# 31813B.net
KiCad netlist of a schematic drawn in EAGLE
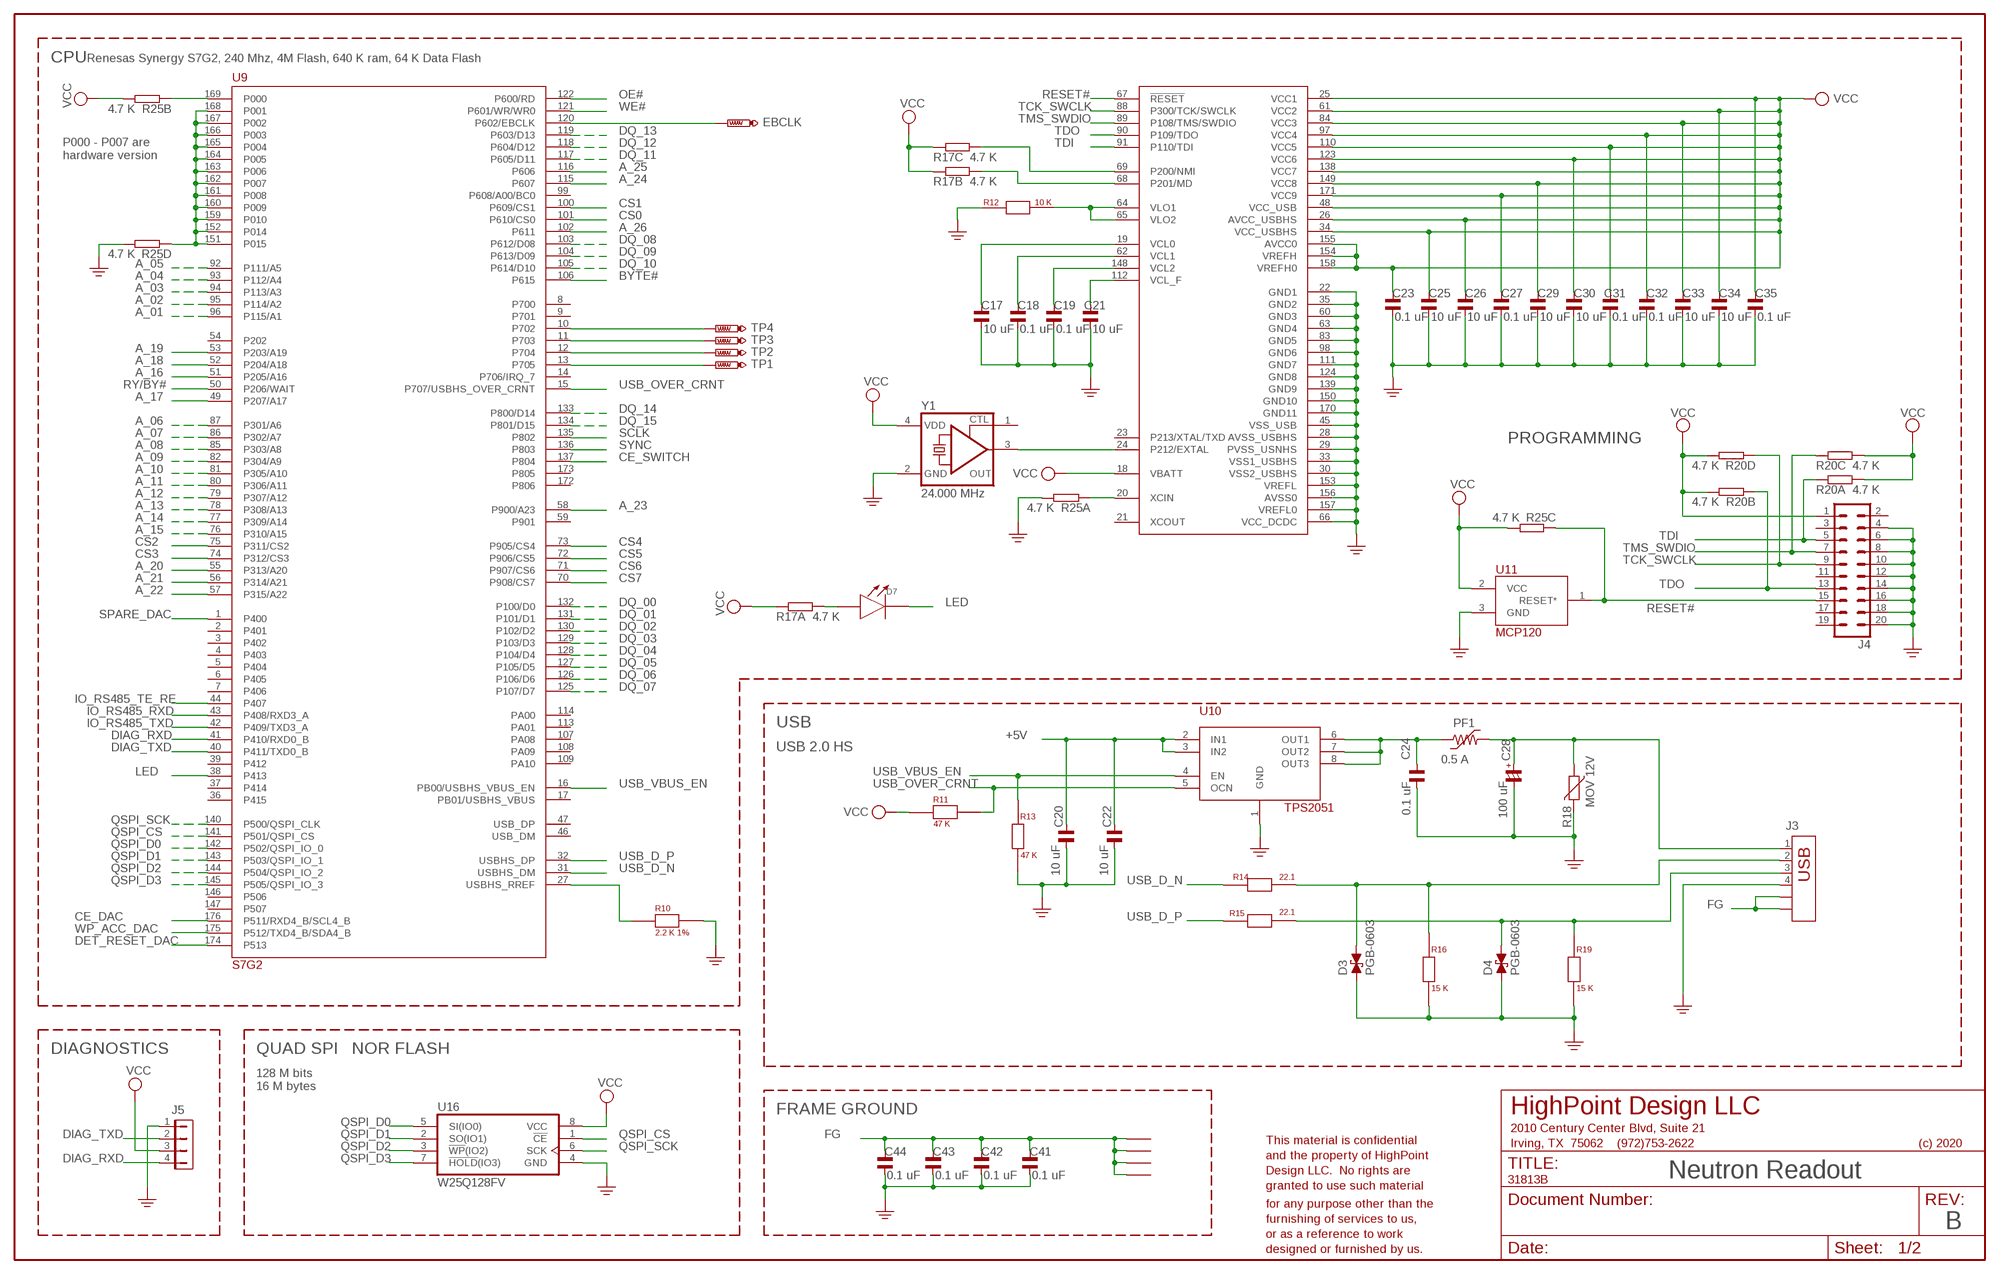
[diagram p0: schematic, sheet 1]
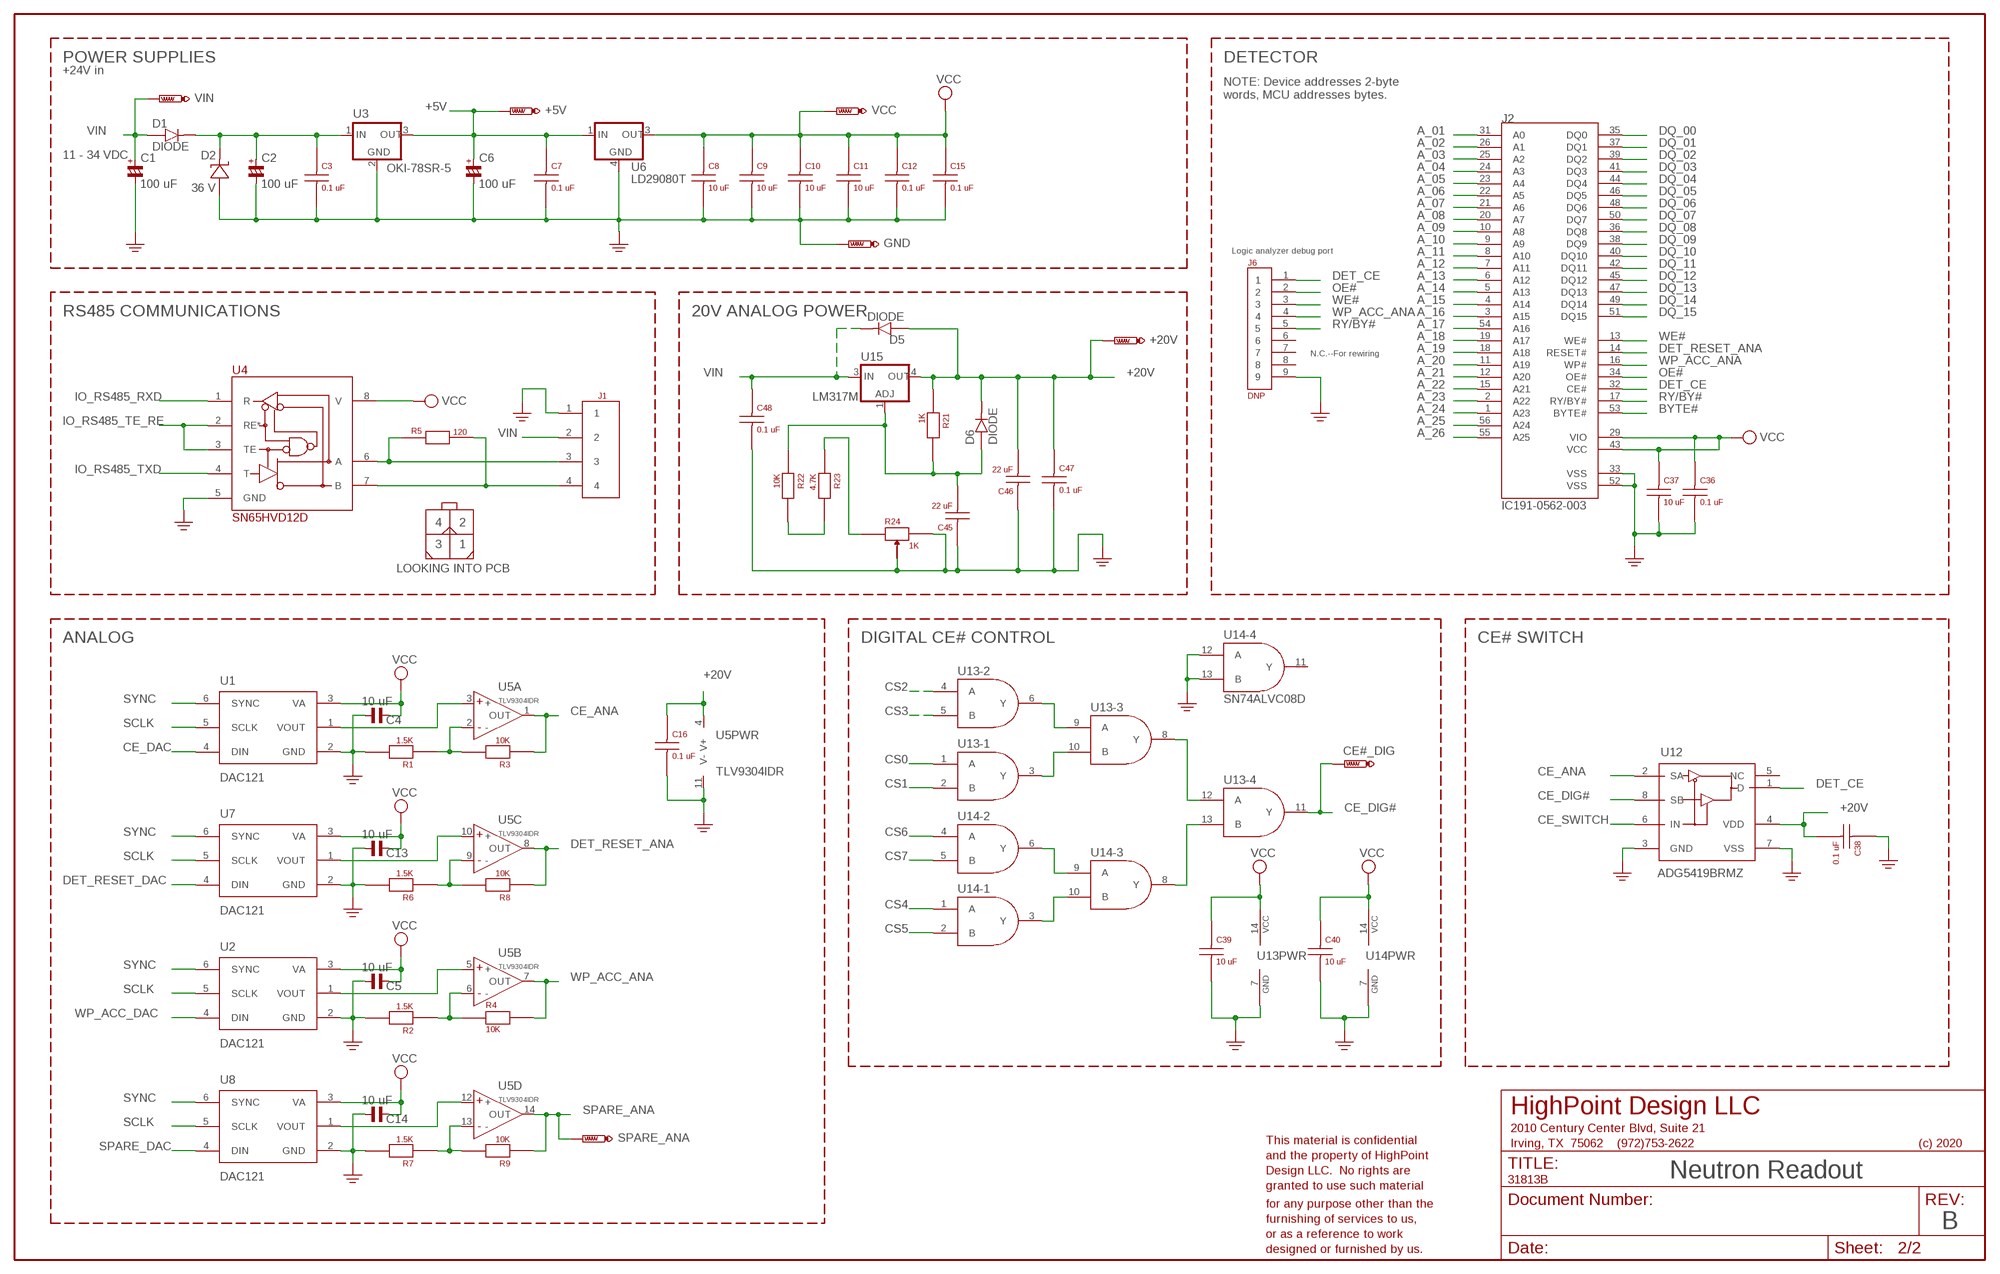
[diagram p1: schematic, sheet 2]

(export (version "E")
  (design (tool "Eeschema 10.0.6"))
  (components
    (comp (ref "C17")
      (value "10 uF")
      (footprint "eagle-import:0603")
      (libsource (lib "eagle-import") (part "CAP_SMD-0603"))
    )
    (comp (ref "C18")
      (value "0.1 uF")
      (footprint "eagle-import:0603")
      (libsource (lib "eagle-import") (part "CAP_SMD-0603"))
    )
    (comp (ref "C19")
      (value "0.1 uF")
      (footprint "eagle-import:0603")
      (libsource (lib "eagle-import") (part "CAP_SMD-0603"))
    )
    (comp (ref "C20")
      (value "10 uF")
      (footprint "eagle-import:0603")
      (libsource (lib "eagle-import") (part "CAP_SMD-0603"))
    )
    (comp (ref "C21")
      (value "10 uF")
      (footprint "eagle-import:0603")
      (libsource (lib "eagle-import") (part "CAP_SMD-0603"))
    )
    (comp (ref "C22")
      (value "10 uF")
      (footprint "eagle-import:0603")
      (libsource (lib "eagle-import") (part "CAP_SMD-0603"))
    )
    (comp (ref "C23")
      (value "0.1 uF")
      (footprint "eagle-import:0603")
      (libsource (lib "eagle-import") (part "CAP_SMD-0603"))
    )
    (comp (ref "C24")
      (value "0.1 uF")
      (footprint "eagle-import:0603")
      (libsource (lib "eagle-import") (part "CAP_SMD-0603"))
    )
    (comp (ref "C25")
      (value "10 uF")
      (footprint "eagle-import:0603")
      (libsource (lib "eagle-import") (part "CAP_SMD-0603"))
    )
    (comp (ref "C26")
      (value "10 uF")
      (footprint "eagle-import:0603")
      (libsource (lib "eagle-import") (part "CAP_SMD-0603"))
    )
    (comp (ref "C27")
      (value "0.1 uF")
      (footprint "eagle-import:0603")
      (libsource (lib "eagle-import") (part "CAP_SMD-0603"))
    )
    (comp (ref "C28")
      (value "100 uF")
      (footprint "eagle-import:CSV-E_F")
      (libsource (lib "eagle-import") (part "CAP_POL-E"))
    )
    (comp (ref "C29")
      (value "10 uF")
      (footprint "eagle-import:0603")
      (libsource (lib "eagle-import") (part "CAP_SMD-0603"))
    )
    (comp (ref "C30")
      (value "10 uF")
      (footprint "eagle-import:0603")
      (libsource (lib "eagle-import") (part "CAP_SMD-0603"))
    )
    (comp (ref "C31")
      (value "0.1 uF")
      (footprint "eagle-import:0603")
      (libsource (lib "eagle-import") (part "CAP_SMD-0603"))
    )
    (comp (ref "C32")
      (value "0.1 uF")
      (footprint "eagle-import:0603")
      (libsource (lib "eagle-import") (part "CAP_SMD-0603"))
    )
    (comp (ref "C33")
      (value "10 uF")
      (footprint "eagle-import:0603")
      (libsource (lib "eagle-import") (part "CAP_SMD-0603"))
    )
    (comp (ref "C34")
      (value "10 uF")
      (footprint "eagle-import:0603")
      (libsource (lib "eagle-import") (part "CAP_SMD-0603"))
    )
    (comp (ref "C35")
      (value "0.1 uF")
      (footprint "eagle-import:0603")
      (libsource (lib "eagle-import") (part "CAP_SMD-0603"))
    )
    (comp (ref "C41")
      (value "0.1 uF")
      (footprint "eagle-import:0603")
      (libsource (lib "eagle-import") (part "CAP_SMD-0603"))
    )
    (comp (ref "C42")
      (value "0.1 uF")
      (footprint "eagle-import:0603")
      (libsource (lib "eagle-import") (part "CAP_SMD-0603"))
    )
    (comp (ref "C43")
      (value "0.1 uF")
      (footprint "eagle-import:0603")
      (libsource (lib "eagle-import") (part "CAP_SMD-0603"))
    )
    (comp (ref "C44")
      (value "0.1 uF")
      (footprint "eagle-import:0603")
      (libsource (lib "eagle-import") (part "CAP_SMD-0603"))
    )
    (comp (ref "D3")
      (value "PGB-0603")
      (footprint "eagle-import:PGB-0603")
      (libsource (lib "eagle-import") (part "PGB-0603"))
    )
    (comp (ref "D4")
      (value "PGB-0603")
      (footprint "eagle-import:PGB-0603")
      (libsource (lib "eagle-import") (part "PGB-0603"))
    )
    (comp (ref "D7")
      (value "LED0805")
      (footprint "eagle-import:D0805")
      (libsource (lib "eagle-import") (part "LED0805"))
    )
    (comp (ref "EBCLK")
      (value "TP")
      (footprint "eagle-import:TP8040")
      (libsource (lib "eagle-import") (part "TP"))
    )
    (comp (ref "J3")
      (value "CON-USB-292303-1")
      (footprint "eagle-import:USB")
      (libsource (lib "eagle-import") (part "CON-USB-292303-1"))
    )
    (comp (ref "J4")
      (value "ML20")
      (footprint "eagle-import:ML20")
      (libsource (lib "eagle-import") (part "ML20"))
    )
    (comp (ref "J5")
      (value "MTA04")
      (footprint "eagle-import:MTA04-100")
      (libsource (lib "eagle-import") (part "MTA04"))
    )
    (comp (ref "M1")
      (value "MNT-125")
      (footprint "eagle-import:MNT-125")
      (libsource (lib "eagle-import") (part "MNT-125"))
    )
    (comp (ref "M2")
      (value "MNT-125")
      (footprint "eagle-import:MNT-125")
      (libsource (lib "eagle-import") (part "MNT-125"))
    )
    (comp (ref "M3")
      (value "MNT-125")
      (footprint "eagle-import:MNT-125")
      (libsource (lib "eagle-import") (part "MNT-125"))
    )
    (comp (ref "M4")
      (value "MNT-125")
      (footprint "eagle-import:MNT-125")
      (libsource (lib "eagle-import") (part "MNT-125"))
    )
    (comp (ref "PF1")
      (value "0.5 A")
      (footprint "eagle-import:F1206")
      (libsource (lib "eagle-import") (part "PTC-F1206"))
    )
    (comp (ref "R10")
      (value "2.2 K 1%")
      (footprint "eagle-import:0603")
      (libsource (lib "eagle-import") (part "RES-0603-H"))
    )
    (comp (ref "R11")
      (value "47 K")
      (footprint "eagle-import:0603")
      (libsource (lib "eagle-import") (part "RES-0603-H"))
    )
    (comp (ref "R12")
      (value "10 K")
      (footprint "eagle-import:0603")
      (libsource (lib "eagle-import") (part "RES-0603-H"))
    )
    (comp (ref "R13")
      (value "47 K")
      (footprint "eagle-import:0603")
      (libsource (lib "eagle-import") (part "RES-0603-V"))
    )
    (comp (ref "R14")
      (value "22.1")
      (footprint "eagle-import:0603")
      (libsource (lib "eagle-import") (part "RES-0603-H"))
    )
    (comp (ref "R15")
      (value "22.1")
      (footprint "eagle-import:0603")
      (libsource (lib "eagle-import") (part "RES-0603-H"))
    )
    (comp (ref "R16")
      (value "15 K")
      (footprint "eagle-import:0603")
      (libsource (lib "eagle-import") (part "RES-0603-V"))
    )
    (comp (ref "R17")
      (value "4.7 K")
      (footprint "eagle-import:RNET-4R-38V")
      (libsource (lib "eagle-import") (part "R_38V"))
    )
    (comp (ref "R18")
      (value "MOV 12V")
      (footprint "eagle-import:R0603")
      (libsource (lib "eagle-import") (part "VARISTOR-0603"))
    )
    (comp (ref "R19")
      (value "15 K")
      (footprint "eagle-import:0603")
      (libsource (lib "eagle-import") (part "RES-0603-V"))
    )
    (comp (ref "R20")
      (value "4.7 K")
      (footprint "eagle-import:RNET-4R-38V")
      (libsource (lib "eagle-import") (part "R_38V"))
    )
    (comp (ref "R25")
      (value "4.7 K")
      (footprint "eagle-import:RNET-4R-38V")
      (libsource (lib "eagle-import") (part "R_38V"))
    )
    (comp (ref "TP1")
      (value "TP")
      (footprint "eagle-import:TP8040")
      (libsource (lib "eagle-import") (part "TP"))
    )
    (comp (ref "TP2")
      (value "TP")
      (footprint "eagle-import:TP8040")
      (libsource (lib "eagle-import") (part "TP"))
    )
    (comp (ref "TP3")
      (value "TP")
      (footprint "eagle-import:TP8040")
      (libsource (lib "eagle-import") (part "TP"))
    )
    (comp (ref "TP4")
      (value "TP")
      (footprint "eagle-import:TP8040")
      (libsource (lib "eagle-import") (part "TP"))
    )
    (comp (ref "U9")
      (value "S7G2")
      (footprint "eagle-import:LQFP176")
      (libsource (lib "eagle-import") (part "S7G2-176"))
    )
    (comp (ref "U10")
      (value "TPS2051")
      (footprint "eagle-import:SOIC-8-SPECIAL")
      (libsource (lib "eagle-import") (part "TPS2051"))
    )
    (comp (ref "U11")
      (value "MCP120")
      (footprint "eagle-import:SOT23")
      (libsource (lib "eagle-import") (part "MCP120"))
    )
    (comp (ref "U16")
      (value "W25Q128FV")
      (footprint "eagle-import:SO08-JB")
      (libsource (lib "eagle-import") (part "IS25LQ080B-JB"))
    )
    (comp (ref "Y1")
      (value "24.000 MHz")
      (footprint "eagle-import:ASFL1")
      (libsource (lib "eagle-import") (part "ASFL1"))
    )
    (comp (ref "+5V")
      (value "TP")
      (footprint "eagle-import:TP8040")
      (libsource (lib "eagle-import") (part "TP"))
    )
    (comp (ref "+20V")
      (value "TP")
      (footprint "eagle-import:TP8040")
      (libsource (lib "eagle-import") (part "TP"))
    )
    (comp (ref "C1")
      (value "100 uF")
      (footprint "eagle-import:CSV-E_F")
      (libsource (lib "eagle-import") (part "CAP_POL-E"))
    )
    (comp (ref "C2")
      (value "100 uF")
      (footprint "eagle-import:CSV-E_F")
      (libsource (lib "eagle-import") (part "CAP_POL-E"))
    )
    (comp (ref "C3")
      (value "0.1 uF")
      (footprint "eagle-import:0603")
      (libsource (lib "eagle-import") (part "CAP-0603"))
    )
    (comp (ref "C4")
      (value "10 uF")
      (footprint "eagle-import:0603")
      (libsource (lib "eagle-import") (part "CAP_SMD-0603"))
    )
    (comp (ref "C5")
      (value "10 uF")
      (footprint "eagle-import:0603")
      (libsource (lib "eagle-import") (part "CAP_SMD-0603"))
    )
    (comp (ref "C6")
      (value "100 uF")
      (footprint "eagle-import:CSV-E_F")
      (libsource (lib "eagle-import") (part "CAP_POL-E"))
    )
    (comp (ref "C7")
      (value "0.1 uF")
      (footprint "eagle-import:0603")
      (libsource (lib "eagle-import") (part "CAP-0603"))
    )
    (comp (ref "C8")
      (value "10 uF")
      (footprint "eagle-import:0603")
      (libsource (lib "eagle-import") (part "CAP-0603"))
    )
    (comp (ref "C9")
      (value "10 uF")
      (footprint "eagle-import:0603")
      (libsource (lib "eagle-import") (part "CAP-0603"))
    )
    (comp (ref "C10")
      (value "10 uF")
      (footprint "eagle-import:0603")
      (libsource (lib "eagle-import") (part "CAP-0603"))
    )
    (comp (ref "C11")
      (value "10 uF")
      (footprint "eagle-import:0603")
      (libsource (lib "eagle-import") (part "CAP-0603"))
    )
    (comp (ref "C12")
      (value "0.1 uF")
      (footprint "eagle-import:0603")
      (libsource (lib "eagle-import") (part "CAP-0603"))
    )
    (comp (ref "C13")
      (value "10 uF")
      (footprint "eagle-import:0603")
      (libsource (lib "eagle-import") (part "CAP_SMD-0603"))
    )
    (comp (ref "C14")
      (value "10 uF")
      (footprint "eagle-import:0603")
      (libsource (lib "eagle-import") (part "CAP_SMD-0603"))
    )
    (comp (ref "C15")
      (value "0.1 uF")
      (footprint "eagle-import:0603")
      (libsource (lib "eagle-import") (part "CAP-0603"))
    )
    (comp (ref "C16")
      (value "0.1 uF")
      (footprint "eagle-import:0603")
      (libsource (lib "eagle-import") (part "CAP-0603"))
    )
    (comp (ref "C36")
      (value "0.1 uF")
      (footprint "eagle-import:0603")
      (libsource (lib "eagle-import") (part "CAP-0603"))
    )
    (comp (ref "C37")
      (value "10 uF")
      (footprint "eagle-import:0603")
      (libsource (lib "eagle-import") (part "CAP-0603"))
    )
    (comp (ref "C38")
      (value "0.1 uF")
      (footprint "eagle-import:0603")
      (libsource (lib "eagle-import") (part "CAP-0603"))
    )
    (comp (ref "C39")
      (value "10 uF")
      (footprint "eagle-import:0603")
      (libsource (lib "eagle-import") (part "CAP-0603"))
    )
    (comp (ref "C40")
      (value "10 uF")
      (footprint "eagle-import:0603")
      (libsource (lib "eagle-import") (part "CAP-0603"))
    )
    (comp (ref "C45")
      (value "22 uF")
      (footprint "eagle-import:C1206")
      (libsource (lib "eagle-import") (part "CAP-1206"))
    )
    (comp (ref "C46")
      (value "22 uF")
      (footprint "eagle-import:C1206")
      (libsource (lib "eagle-import") (part "CAP-1206"))
    )
    (comp (ref "C47")
      (value "0.1 uF")
      (footprint "eagle-import:0603")
      (libsource (lib "eagle-import") (part "CAP-0603"))
    )
    (comp (ref "C48")
      (value "0.1 uF")
      (footprint "eagle-import:0603")
      (libsource (lib "eagle-import") (part "CAP-0603"))
    )
    (comp (ref "CE#_DIG")
      (value "TP")
      (footprint "eagle-import:TP8040")
      (libsource (lib "eagle-import") (part "TP"))
    )
    (comp (ref "D1")
      (value "DIODE")
      (footprint "eagle-import:SOD-123_MINI-SMA")
      (libsource (lib "eagle-import") (part "DIODE"))
    )
    (comp (ref "D2")
      (value "36 V")
      (footprint "eagle-import:SMB")
      (libsource (lib "eagle-import") (part "TRANSORB"))
    )
    (comp (ref "D5")
      (value "DIODE")
      (footprint "eagle-import:SOD-123_MINI-SMA")
      (libsource (lib "eagle-import") (part "DIODE"))
    )
    (comp (ref "D6")
      (value "DIODE")
      (footprint "eagle-import:SOD-123_MINI-SMA")
      (libsource (lib "eagle-import") (part "DIODE"))
    )
    (comp (ref "GND")
      (value "TP")
      (footprint "eagle-import:TP8040")
      (libsource (lib "eagle-import") (part "TP"))
    )
    (comp (ref "J1")
      (value "MICRO-FIT-4POS")
      (footprint "eagle-import:43045-0412")
      (libsource (lib "eagle-import") (part "MICRO-FIT-4POS"))
    )
    (comp (ref "J2")
      (value "IC191-0562-003")
      (footprint "eagle-import:IC1910562003")
      (fields (field (name "MOUSER_PART_NUMBER") "945-IC191-0562-003"))
      (libsource (lib "eagle-import") (part "IC191-0562-003"))
    )
    (comp (ref "J6")
      (value "DNP")
      (footprint "eagle-import:9P-100")
      (libsource (lib "eagle-import") (part "CON-9P-100"))
    )
    (comp (ref "R1")
      (value "1.5K")
      (footprint "eagle-import:0603")
      (libsource (lib "eagle-import") (part "RES-0603-H"))
    )
    (comp (ref "R2")
      (value "1.5K")
      (footprint "eagle-import:0603")
      (libsource (lib "eagle-import") (part "RES-0603-H"))
    )
    (comp (ref "R3")
      (value "10K")
      (footprint "eagle-import:0603")
      (libsource (lib "eagle-import") (part "RES-0603-H"))
    )
    (comp (ref "R4")
      (value "10K")
      (footprint "eagle-import:0603")
      (libsource (lib "eagle-import") (part "RES-0603-H"))
    )
    (comp (ref "R5")
      (value "120")
      (footprint "eagle-import:0603")
      (libsource (lib "eagle-import") (part "RES-0603-H"))
    )
    (comp (ref "R6")
      (value "1.5K")
      (footprint "eagle-import:0603")
      (libsource (lib "eagle-import") (part "RES-0603-H"))
    )
    (comp (ref "R7")
      (value "1.5K")
      (footprint "eagle-import:0603")
      (libsource (lib "eagle-import") (part "RES-0603-H"))
    )
    (comp (ref "R8")
      (value "10K")
      (footprint "eagle-import:0603")
      (libsource (lib "eagle-import") (part "RES-0603-H"))
    )
    (comp (ref "R9")
      (value "10K")
      (footprint "eagle-import:0603")
      (libsource (lib "eagle-import") (part "RES-0603-H"))
    )
    (comp (ref "R21")
      (value "1K")
      (footprint "eagle-import:0603")
      (libsource (lib "eagle-import") (part "RES-0603-H"))
    )
    (comp (ref "R22")
      (value "10K")
      (footprint "eagle-import:0603")
      (libsource (lib "eagle-import") (part "RES-0603-H"))
    )
    (comp (ref "R23")
      (value "4.7K")
      (footprint "eagle-import:0603")
      (libsource (lib "eagle-import") (part "RES-0603-H"))
    )
    (comp (ref "R24")
      (value "1K")
      (footprint "eagle-import:POT-V10")
      (libsource (lib "eagle-import") (part "PT10XV10"))
    )
    (comp (ref "SPARE_ANA")
      (value "TP")
      (footprint "eagle-import:TP8040")
      (libsource (lib "eagle-import") (part "TP"))
    )
    (comp (ref "U1")
      (value "DAC121")
      (footprint "eagle-import:SOT23-6")
      (libsource (lib "eagle-import") (part "DAC121"))
    )
    (comp (ref "U2")
      (value "DAC121")
      (footprint "eagle-import:SOT23-6")
      (libsource (lib "eagle-import") (part "DAC121"))
    )
    (comp (ref "U3")
      (value "OKI-78SR-5")
      (footprint "eagle-import:PS-OKI-78SR")
      (libsource (lib "eagle-import") (part "PS-OKI-78SR"))
    )
    (comp (ref "U4")
      (value "SN65HVD12D")
      (footprint "eagle-import:SOIC-08-150")
      (libsource (lib "eagle-import") (part "SN65HVD12D"))
    )
    (comp (ref "U5")
      (value "TLV9304IDR")
      (footprint "eagle-import:SO14")
      (libsource (lib "eagle-import") (part "TLV9304IDR"))
    )
    (comp (ref "U6")
      (value "LD29080T")
      (footprint "eagle-import:DPAK")
      (libsource (lib "eagle-import") (part "LD29080T"))
    )
    (comp (ref "U7")
      (value "DAC121")
      (footprint "eagle-import:SOT23-6")
      (libsource (lib "eagle-import") (part "DAC121"))
    )
    (comp (ref "U8")
      (value "DAC121")
      (footprint "eagle-import:SOT23-6")
      (libsource (lib "eagle-import") (part "DAC121"))
    )
    (comp (ref "U12")
      (value "ADG5419BRMZ")
      (footprint "eagle-import:RM_8_ADI")
      (libsource (lib "eagle-import") (part "ADG5419BRMZ"))
    )
    (comp (ref "U13")
      (value "SN74ALVC08D")
      (footprint "eagle-import:D14")
      (fields
        (field (name "GENERIC_PART_NUMBER") "SN74ALVC08")
        (field (name "MANUFACTURER") "Texas Instruments")
      )
      (libsource (lib "eagle-import") (part "SN74ALVC08D"))
    )
    (comp (ref "U14")
      (value "SN74ALVC08D")
      (footprint "eagle-import:D14")
      (fields
        (field (name "GENERIC_PART_NUMBER") "SN74ALVC08")
        (field (name "MANUFACTURER") "Texas Instruments")
      )
      (libsource (lib "eagle-import") (part "SN74ALVC08D"))
    )
    (comp (ref "U15")
      (value "LM317M")
      (footprint "eagle-import:DPAK")
      (libsource (lib "eagle-import") (part "LM317M"))
    )
    (comp (ref "VCC")
      (value "TP")
      (footprint "eagle-import:TP8040")
      (libsource (lib "eagle-import") (part "TP"))
    )
    (comp (ref "VIN")
      (value "TP")
      (footprint "eagle-import:TP8040")
      (libsource (lib "eagle-import") (part "TP"))
    )
  )
  (nets
    (net (code "1") (name "+5V") (class "Default")
      (node (ref "+5V") (pin "1") (pinfunction "TP_1") (pintype "input"))
      (node (ref "C20") (pin "2") (pinfunction "2_2") (pintype "passive"))
      (node (ref "C22") (pin "2") (pinfunction "2_2") (pintype "passive"))
      (node (ref "C6") (pin "+") (pinfunction "+_+") (pintype "passive"))
      (node (ref "C7") (pin "1") (pinfunction "P$1_1") (pintype "bidirectional"))
      (node (ref "U10") (pin "2") (pinfunction "IN1_2") (pintype "bidirectional"))
      (node (ref "U10") (pin "3") (pinfunction "IN2_3") (pintype "bidirectional"))
      (node (ref "U3") (pin "3") (pinfunction "OUT_3") (pintype "passive"))
      (node (ref "U6") (pin "1") (pinfunction "IN_1") (pintype "input"))
    )
    (net (code "2") (name "+20V") (class "Default")
      (node (ref "+20V") (pin "1") (pinfunction "TP_1") (pintype "input"))
      (node (ref "C16") (pin "1") (pinfunction "P$1_1") (pintype "bidirectional"))
      (node (ref "C38") (pin "2") (pinfunction "P$2_2") (pintype "bidirectional"))
      (node (ref "C46") (pin "2") (pinfunction "P$2_2") (pintype "bidirectional"))
      (node (ref "C47") (pin "1") (pinfunction "P$1_1") (pintype "bidirectional"))
      (node (ref "D5") (pin "A") (pinfunction "A_A") (pintype "passive"))
      (node (ref "D6") (pin "C") (pinfunction "C_C") (pintype "passive"))
      (node (ref "R21") (pin "1") (pinfunction "P$1_1") (pintype "bidirectional"))
      (node (ref "U12") (pin "4") (pinfunction "VDD_4") (pintype "passive"))
      (node (ref "U15") (pin "4") (pinfunction "OUT_4") (pintype "passive"))
      (node (ref "U5") (pin "4") (pinfunction "V+_4") (pintype "power_in"))
    )
    (net (code "3") (name "A_01") (class "Default")
      (node (ref "J2") (pin "31") (pinfunction "A0_31") (pintype "input"))
      (node (ref "U9") (pin "96") (pinfunction "P115/A1_96") (pintype "bidirectional"))
    )
    (net (code "4") (name "A_02") (class "Default")
      (node (ref "J2") (pin "26") (pinfunction "A1_26") (pintype "input"))
      (node (ref "U9") (pin "95") (pinfunction "P114/A2_95") (pintype "bidirectional"))
    )
    (net (code "5") (name "A_03") (class "Default")
      (node (ref "J2") (pin "25") (pinfunction "A2_25") (pintype "input"))
      (node (ref "U9") (pin "94") (pinfunction "P113/A3_94") (pintype "bidirectional"))
    )
    (net (code "6") (name "A_04") (class "Default")
      (node (ref "J2") (pin "24") (pinfunction "A3_24") (pintype "input"))
      (node (ref "U9") (pin "93") (pinfunction "P112/A4_93") (pintype "bidirectional"))
    )
    (net (code "7") (name "A_05") (class "Default")
      (node (ref "J2") (pin "23") (pinfunction "A4_23") (pintype "input"))
      (node (ref "U9") (pin "92") (pinfunction "P111/A5_92") (pintype "bidirectional"))
    )
    (net (code "8") (name "A_06") (class "Default")
      (node (ref "J2") (pin "22") (pinfunction "A5_22") (pintype "input"))
      (node (ref "U9") (pin "87") (pinfunction "P301/A6_87") (pintype "bidirectional"))
    )
    (net (code "9") (name "A_07") (class "Default")
      (node (ref "J2") (pin "21") (pinfunction "A6_21") (pintype "input"))
      (node (ref "U9") (pin "86") (pinfunction "P302/A7_86") (pintype "bidirectional"))
    )
    (net (code "10") (name "A_08") (class "Default")
      (node (ref "J2") (pin "20") (pinfunction "A7_20") (pintype "input"))
      (node (ref "U9") (pin "85") (pinfunction "P303/A8_85") (pintype "bidirectional"))
    )
    (net (code "11") (name "A_09") (class "Default")
      (node (ref "J2") (pin "10") (pinfunction "A8_10") (pintype "input"))
      (node (ref "U9") (pin "82") (pinfunction "P304/A9_82") (pintype "bidirectional"))
    )
    (net (code "12") (name "A_10") (class "Default")
      (node (ref "J2") (pin "9") (pinfunction "A9_9") (pintype "input"))
      (node (ref "U9") (pin "81") (pinfunction "P305/A10_81") (pintype "bidirectional"))
    )
    (net (code "13") (name "A_11") (class "Default")
      (node (ref "J2") (pin "8") (pinfunction "A10_8") (pintype "input"))
      (node (ref "U9") (pin "80") (pinfunction "P306/A11_80") (pintype "bidirectional"))
    )
    (net (code "14") (name "A_12") (class "Default")
      (node (ref "J2") (pin "7") (pinfunction "A11_7") (pintype "input"))
      (node (ref "U9") (pin "79") (pinfunction "P307/A12_79") (pintype "bidirectional"))
    )
    (net (code "15") (name "A_13") (class "Default")
      (node (ref "J2") (pin "6") (pinfunction "A12_6") (pintype "input"))
      (node (ref "U9") (pin "78") (pinfunction "P308/A13_78") (pintype "bidirectional"))
    )
    (net (code "16") (name "A_14") (class "Default")
      (node (ref "J2") (pin "5") (pinfunction "A13_5") (pintype "input"))
      (node (ref "U9") (pin "77") (pinfunction "P309/A14_77") (pintype "bidirectional"))
    )
    (net (code "17") (name "A_15") (class "Default")
      (node (ref "J2") (pin "4") (pinfunction "A14_4") (pintype "input"))
      (node (ref "U9") (pin "76") (pinfunction "P310/A15_76") (pintype "bidirectional"))
    )
    (net (code "18") (name "A_16") (class "Default")
      (node (ref "J2") (pin "3") (pinfunction "A15_3") (pintype "input"))
      (node (ref "U9") (pin "51") (pinfunction "P205/A16_51") (pintype "bidirectional"))
    )
    (net (code "19") (name "A_17") (class "Default")
      (node (ref "J2") (pin "54") (pinfunction "A16_54") (pintype "input"))
      (node (ref "U9") (pin "49") (pinfunction "P207/A17_49") (pintype "bidirectional"))
    )
    (net (code "20") (name "A_18") (class "Default")
      (node (ref "J2") (pin "19") (pinfunction "A17_19") (pintype "input"))
      (node (ref "U9") (pin "52") (pinfunction "P204/A18_52") (pintype "bidirectional"))
    )
    (net (code "21") (name "A_19") (class "Default")
      (node (ref "J2") (pin "18") (pinfunction "A18_18") (pintype "input"))
      (node (ref "U9") (pin "53") (pinfunction "P203/A19_53") (pintype "bidirectional"))
    )
    (net (code "22") (name "A_20") (class "Default")
      (node (ref "J2") (pin "11") (pinfunction "A19_11") (pintype "input"))
      (node (ref "U9") (pin "55") (pinfunction "P313/A20_55") (pintype "bidirectional"))
    )
    (net (code "23") (name "A_21") (class "Default")
      (node (ref "J2") (pin "12") (pinfunction "A20_12") (pintype "input"))
      (node (ref "U9") (pin "56") (pinfunction "P314/A21_56") (pintype "bidirectional"))
    )
    (net (code "24") (name "A_22") (class "Default")
      (node (ref "J2") (pin "15") (pinfunction "A21_15") (pintype "input"))
      (node (ref "U9") (pin "57") (pinfunction "P315/A22_57") (pintype "bidirectional"))
    )
    (net (code "25") (name "A_23") (class "Default")
      (node (ref "J2") (pin "2") (pinfunction "A22_2") (pintype "input"))
      (node (ref "U9") (pin "58") (pinfunction "P900/A23_58") (pintype "bidirectional"))
    )
    (net (code "26") (name "A_24") (class "Default")
      (node (ref "J2") (pin "1") (pinfunction "A23_1") (pintype "input"))
      (node (ref "U9") (pin "115") (pinfunction "P607_115") (pintype "bidirectional"))
    )
    (net (code "27") (name "A_25") (class "Default")
      (node (ref "J2") (pin "56") (pinfunction "A24_56") (pintype "input"))
      (node (ref "U9") (pin "116") (pinfunction "P606_116") (pintype "bidirectional"))
    )
    (net (code "28") (name "A_26") (class "Default")
      (node (ref "J2") (pin "55") (pinfunction "A25_55") (pintype "input"))
      (node (ref "U9") (pin "102") (pinfunction "P611_102") (pintype "bidirectional"))
    )
    (net (code "29") (name "BYTE#") (class "Default")
      (node (ref "J2") (pin "53") (pinfunction "BYTE#_53") (pintype "input"))
      (node (ref "U9") (pin "106") (pinfunction "P615_106") (pintype "bidirectional"))
    )
    (net (code "30") (name "CE_ANA") (class "Default")
      (node (ref "R3") (pin "1") (pinfunction "P$1_1") (pintype "bidirectional"))
      (node (ref "U12") (pin "2") (pinfunction "SA_2") (pintype "passive"))
      (node (ref "U5") (pin "1") (pinfunction "OUT_1") (pintype "output"))
    )
    (net (code "31") (name "CE_DAC") (class "Default")
      (node (ref "U1") (pin "4") (pinfunction "DIN_4") (pintype "input"))
      (node (ref "U9") (pin "176") (pinfunction "P511/RXD4_B/SCL4_B_176") (pintype "bidirectional"))
    )
    (net (code "32") (name "CE_DIG#") (class "Default")
      (node (ref "CE#_DIG") (pin "1") (pinfunction "TP_1") (pintype "input"))
      (node (ref "U12") (pin "8") (pinfunction "SB_8") (pintype "passive"))
      (node (ref "U13") (pin "11") (pinfunction "Y_11") (pintype "output"))
    )
    (net (code "33") (name "CE_SWITCH") (class "Default")
      (node (ref "U12") (pin "6") (pinfunction "IN_6") (pintype "passive"))
      (node (ref "U9") (pin "137") (pinfunction "P804_137") (pintype "bidirectional"))
    )
    (net (code "34") (name "CS0") (class "Default")
      (node (ref "U13") (pin "1") (pinfunction "A_1") (pintype "input"))
      (node (ref "U9") (pin "101") (pinfunction "P610/CS0_101") (pintype "bidirectional"))
    )
    (net (code "35") (name "CS1") (class "Default")
      (node (ref "U13") (pin "2") (pinfunction "B_2") (pintype "input"))
      (node (ref "U9") (pin "100") (pinfunction "P609/CS1_100") (pintype "bidirectional"))
    )
    (net (code "36") (name "CS2") (class "Default")
      (node (ref "U13") (pin "4") (pinfunction "A_4") (pintype "input"))
      (node (ref "U9") (pin "75") (pinfunction "P311/CS2_75") (pintype "bidirectional"))
    )
    (net (code "37") (name "CS3") (class "Default")
      (node (ref "U13") (pin "5") (pinfunction "B_5") (pintype "input"))
      (node (ref "U9") (pin "74") (pinfunction "P312/CS3_74") (pintype "bidirectional"))
    )
    (net (code "38") (name "CS4") (class "Default")
      (node (ref "U14") (pin "1") (pinfunction "A_1") (pintype "input"))
      (node (ref "U9") (pin "73") (pinfunction "P905/CS4_73") (pintype "bidirectional"))
    )
    (net (code "39") (name "CS5") (class "Default")
      (node (ref "U14") (pin "2") (pinfunction "B_2") (pintype "input"))
      (node (ref "U9") (pin "72") (pinfunction "P906/CS5_72") (pintype "bidirectional"))
    )
    (net (code "40") (name "CS6") (class "Default")
      (node (ref "U14") (pin "4") (pinfunction "A_4") (pintype "input"))
      (node (ref "U9") (pin "71") (pinfunction "P907/CS6_71") (pintype "bidirectional"))
    )
    (net (code "41") (name "CS7") (class "Default")
      (node (ref "U14") (pin "5") (pinfunction "B_5") (pintype "input"))
      (node (ref "U9") (pin "70") (pinfunction "P908/CS7_70") (pintype "bidirectional"))
    )
    (net (code "42") (name "DET_CE") (class "Default")
      (node (ref "J2") (pin "32") (pinfunction "CE#_32") (pintype "input"))
      (node (ref "J6") (pin "1") (pinfunction "1_1") (pintype "passive"))
      (node (ref "U12") (pin "1") (pinfunction "D_1") (pintype "passive"))
    )
    (net (code "43") (name "DET_RESET_ANA") (class "Default")
      (node (ref "J2") (pin "14") (pinfunction "RESET#_14") (pintype "input"))
      (node (ref "R8") (pin "1") (pinfunction "P$1_1") (pintype "bidirectional"))
      (node (ref "U5") (pin "8") (pinfunction "OUT_8") (pintype "output"))
    )
    (net (code "44") (name "DET_RESET_DAC") (class "Default")
      (node (ref "U7") (pin "4") (pinfunction "DIN_4") (pintype "input"))
      (node (ref "U9") (pin "174") (pinfunction "P513_174") (pintype "bidirectional"))
    )
    (net (code "45") (name "DIAG_RXD") (class "Default")
      (node (ref "J5") (pin "4") (pinfunction "4_4") (pintype "passive"))
      (node (ref "U9") (pin "41") (pinfunction "P410/RXD0_B_41") (pintype "bidirectional"))
    )
    (net (code "46") (name "DIAG_TXD") (class "Default")
      (node (ref "J5") (pin "2") (pinfunction "2_2") (pintype "passive"))
      (node (ref "U9") (pin "40") (pinfunction "P411/TXD0_B_40") (pintype "bidirectional"))
    )
    (net (code "47") (name "DQ_00") (class "Default")
      (node (ref "J2") (pin "35") (pinfunction "DQ0_35") (pintype "bidirectional"))
      (node (ref "U9") (pin "132") (pinfunction "P100/D0_132") (pintype "bidirectional"))
    )
    (net (code "48") (name "DQ_01") (class "Default")
      (node (ref "J2") (pin "37") (pinfunction "DQ1_37") (pintype "bidirectional"))
      (node (ref "U9") (pin "131") (pinfunction "P101/D1_131") (pintype "bidirectional"))
    )
    (net (code "49") (name "DQ_02") (class "Default")
      (node (ref "J2") (pin "39") (pinfunction "DQ2_39") (pintype "bidirectional"))
      (node (ref "U9") (pin "130") (pinfunction "P102/D2_130") (pintype "bidirectional"))
    )
    (net (code "50") (name "DQ_03") (class "Default")
      (node (ref "J2") (pin "41") (pinfunction "DQ3_41") (pintype "bidirectional"))
      (node (ref "U9") (pin "129") (pinfunction "P103/D3_129") (pintype "bidirectional"))
    )
    (net (code "51") (name "DQ_04") (class "Default")
      (node (ref "J2") (pin "44") (pinfunction "DQ4_44") (pintype "bidirectional"))
      (node (ref "U9") (pin "128") (pinfunction "P104/D4_128") (pintype "bidirectional"))
    )
    (net (code "52") (name "DQ_05") (class "Default")
      (node (ref "J2") (pin "46") (pinfunction "DQ5_46") (pintype "bidirectional"))
      (node (ref "U9") (pin "127") (pinfunction "P105/D5_127") (pintype "bidirectional"))
    )
    (net (code "53") (name "DQ_06") (class "Default")
      (node (ref "J2") (pin "48") (pinfunction "DQ6_48") (pintype "bidirectional"))
      (node (ref "U9") (pin "126") (pinfunction "P106/D6_126") (pintype "bidirectional"))
    )
    (net (code "54") (name "DQ_07") (class "Default")
      (node (ref "J2") (pin "50") (pinfunction "DQ7_50") (pintype "bidirectional"))
      (node (ref "U9") (pin "125") (pinfunction "P107/D7_125") (pintype "bidirectional"))
    )
    (net (code "55") (name "DQ_08") (class "Default")
      (node (ref "J2") (pin "36") (pinfunction "DQ8_36") (pintype "bidirectional"))
      (node (ref "U9") (pin "103") (pinfunction "P612/D08_103") (pintype "bidirectional"))
    )
    (net (code "56") (name "DQ_09") (class "Default")
      (node (ref "J2") (pin "38") (pinfunction "DQ9_38") (pintype "bidirectional"))
      (node (ref "U9") (pin "104") (pinfunction "P613/D09_104") (pintype "bidirectional"))
    )
    (net (code "57") (name "DQ_10") (class "Default")
      (node (ref "J2") (pin "40") (pinfunction "DQ10_40") (pintype "bidirectional"))
      (node (ref "U9") (pin "105") (pinfunction "P614/D10_105") (pintype "bidirectional"))
    )
    (net (code "58") (name "DQ_11") (class "Default")
      (node (ref "J2") (pin "42") (pinfunction "DQ11_42") (pintype "bidirectional"))
      (node (ref "U9") (pin "117") (pinfunction "P605/D11_117") (pintype "bidirectional"))
    )
    (net (code "59") (name "DQ_12") (class "Default")
      (node (ref "J2") (pin "45") (pinfunction "DQ12_45") (pintype "bidirectional"))
      (node (ref "U9") (pin "118") (pinfunction "P604/D12_118") (pintype "bidirectional"))
    )
    (net (code "60") (name "DQ_13") (class "Default")
      (node (ref "J2") (pin "47") (pinfunction "DQ13_47") (pintype "bidirectional"))
      (node (ref "U9") (pin "119") (pinfunction "P603/D13_119") (pintype "bidirectional"))
    )
    (net (code "61") (name "DQ_14") (class "Default")
      (node (ref "J2") (pin "49") (pinfunction "DQ14_49") (pintype "bidirectional"))
      (node (ref "U9") (pin "133") (pinfunction "P800/D14_133") (pintype "bidirectional"))
    )
    (net (code "62") (name "DQ_15") (class "Default")
      (node (ref "J2") (pin "51") (pinfunction "DQ15_51") (pintype "bidirectional"))
      (node (ref "U9") (pin "134") (pinfunction "P801/D15_134") (pintype "bidirectional"))
    )
    (net (code "63") (name "FG") (class "Default")
      (node (ref "C41") (pin "2") (pinfunction "2_2") (pintype "passive"))
      (node (ref "C42") (pin "2") (pinfunction "2_2") (pintype "passive"))
      (node (ref "C43") (pin "2") (pinfunction "2_2") (pintype "passive"))
      (node (ref "C44") (pin "2") (pinfunction "2_2") (pintype "passive"))
      (node (ref "J3") (pin "S1") (pinfunction "S1_S1") (pintype "passive"))
      (node (ref "J3") (pin "S2") (pinfunction "S2_S2") (pintype "passive"))
      (node (ref "M1") (pin "1") (pinfunction "1_1") (pintype "bidirectional"))
      (node (ref "M2") (pin "1") (pinfunction "1_1") (pintype "bidirectional"))
      (node (ref "M3") (pin "1") (pinfunction "1_1") (pintype "bidirectional"))
      (node (ref "M4") (pin "1") (pinfunction "1_1") (pintype "bidirectional"))
    )
    (net (code "64") (name "GND") (class "Default")
      (node (ref "C1") (pin "-") (pinfunction "-_-") (pintype "passive"))
      (node (ref "C10") (pin "2") (pinfunction "P$2_2") (pintype "bidirectional"))
      (node (ref "C11") (pin "2") (pinfunction "P$2_2") (pintype "bidirectional"))
      (node (ref "C12") (pin "2") (pinfunction "P$2_2") (pintype "bidirectional"))
      (node (ref "C13") (pin "1") (pinfunction "1_1") (pintype "passive"))
      (node (ref "C14") (pin "1") (pinfunction "1_1") (pintype "passive"))
      (node (ref "C15") (pin "2") (pinfunction "P$2_2") (pintype "bidirectional"))
      (node (ref "C16") (pin "2") (pinfunction "P$2_2") (pintype "bidirectional"))
      (node (ref "C17") (pin "1") (pinfunction "1_1") (pintype "passive"))
      (node (ref "C18") (pin "1") (pinfunction "1_1") (pintype "passive"))
      (node (ref "C19") (pin "1") (pinfunction "1_1") (pintype "passive"))
      (node (ref "C2") (pin "-") (pinfunction "-_-") (pintype "passive"))
      (node (ref "C20") (pin "1") (pinfunction "1_1") (pintype "passive"))
      (node (ref "C21") (pin "1") (pinfunction "1_1") (pintype "passive"))
      (node (ref "C22") (pin "1") (pinfunction "1_1") (pintype "passive"))
      (node (ref "C23") (pin "1") (pinfunction "1_1") (pintype "passive"))
      (node (ref "C24") (pin "1") (pinfunction "1_1") (pintype "passive"))
      (node (ref "C25") (pin "1") (pinfunction "1_1") (pintype "passive"))
      (node (ref "C26") (pin "1") (pinfunction "1_1") (pintype "passive"))
      (node (ref "C27") (pin "1") (pinfunction "1_1") (pintype "passive"))
      (node (ref "C28") (pin "-") (pinfunction "-_-") (pintype "passive"))
      (node (ref "C29") (pin "1") (pinfunction "1_1") (pintype "passive"))
      (node (ref "C3") (pin "2") (pinfunction "P$2_2") (pintype "bidirectional"))
      (node (ref "C30") (pin "1") (pinfunction "1_1") (pintype "passive"))
      (node (ref "C31") (pin "1") (pinfunction "1_1") (pintype "passive"))
      (node (ref "C32") (pin "1") (pinfunction "1_1") (pintype "passive"))
      (node (ref "C33") (pin "1") (pinfunction "1_1") (pintype "passive"))
      (node (ref "C34") (pin "1") (pinfunction "1_1") (pintype "passive"))
      (node (ref "C35") (pin "1") (pinfunction "1_1") (pintype "passive"))
      (node (ref "C36") (pin "2") (pinfunction "P$2_2") (pintype "bidirectional"))
      (node (ref "C37") (pin "2") (pinfunction "P$2_2") (pintype "bidirectional"))
      (node (ref "C38") (pin "1") (pinfunction "P$1_1") (pintype "bidirectional"))
      (node (ref "C39") (pin "2") (pinfunction "P$2_2") (pintype "bidirectional"))
      (node (ref "C4") (pin "1") (pinfunction "1_1") (pintype "passive"))
      (node (ref "C40") (pin "2") (pinfunction "P$2_2") (pintype "bidirectional"))
      (node (ref "C41") (pin "1") (pinfunction "1_1") (pintype "passive"))
      (node (ref "C42") (pin "1") (pinfunction "1_1") (pintype "passive"))
      (node (ref "C43") (pin "1") (pinfunction "1_1") (pintype "passive"))
      (node (ref "C44") (pin "1") (pinfunction "1_1") (pintype "passive"))
      (node (ref "C45") (pin "1") (pinfunction "P$1_1") (pintype "bidirectional"))
      (node (ref "C46") (pin "1") (pinfunction "P$1_1") (pintype "bidirectional"))
      (node (ref "C47") (pin "2") (pinfunction "P$2_2") (pintype "bidirectional"))
      (node (ref "C48") (pin "2") (pinfunction "P$2_2") (pintype "bidirectional"))
      (node (ref "C5") (pin "1") (pinfunction "1_1") (pintype "passive"))
      (node (ref "C6") (pin "-") (pinfunction "-_-") (pintype "passive"))
      (node (ref "C7") (pin "2") (pinfunction "P$2_2") (pintype "bidirectional"))
      (node (ref "C8") (pin "2") (pinfunction "P$2_2") (pintype "bidirectional"))
      (node (ref "C9") (pin "2") (pinfunction "P$2_2") (pintype "bidirectional"))
      (node (ref "D2") (pin "A") (pinfunction "A_A") (pintype "passive"))
      (node (ref "D3") (pin "1") (pinfunction "1_1") (pintype "passive"))
      (node (ref "D4") (pin "1") (pinfunction "1_1") (pintype "passive"))
      (node (ref "GND") (pin "1") (pinfunction "TP_1") (pintype "input"))
      (node (ref "J1") (pin "1") (pinfunction "1_1") (pintype "bidirectional"))
      (node (ref "J2") (pin "33") (pinfunction "VSS_33") (pintype "power_in"))
      (node (ref "J2") (pin "52") (pinfunction "VSS_52") (pintype "power_in"))
      (node (ref "J3") (pin "4") (pinfunction "4_4") (pintype "passive"))
      (node (ref "J4") (pin "10") (pinfunction "10_10") (pintype "passive"))
      (node (ref "J4") (pin "12") (pinfunction "12_12") (pintype "passive"))
      (node (ref "J4") (pin "14") (pinfunction "14_14") (pintype "passive"))
      (node (ref "J4") (pin "16") (pinfunction "16_16") (pintype "passive"))
      (node (ref "J4") (pin "18") (pinfunction "18_18") (pintype "passive"))
      (node (ref "J4") (pin "20") (pinfunction "20_20") (pintype "passive"))
      (node (ref "J4") (pin "4") (pinfunction "4_4") (pintype "passive"))
      (node (ref "J4") (pin "6") (pinfunction "6_6") (pintype "passive"))
      (node (ref "J4") (pin "8") (pinfunction "8_8") (pintype "passive"))
      (node (ref "J5") (pin "1") (pinfunction "1_1") (pintype "passive"))
      (node (ref "J6") (pin "9") (pinfunction "9_9") (pintype "passive"))
      (node (ref "R1") (pin "2") (pinfunction "P$2_2") (pintype "bidirectional"))
      (node (ref "R10") (pin "2") (pinfunction "P$2_2") (pintype "bidirectional"))
      (node (ref "R12") (pin "1") (pinfunction "P$1_1") (pintype "bidirectional"))
      (node (ref "R13") (pin "1") (pinfunction "P$1_1") (pintype "bidirectional"))
      (node (ref "R16") (pin "1") (pinfunction "P$1_1") (pintype "bidirectional"))
      (node (ref "R18") (pin "2") (pinfunction "2_2") (pintype "passive"))
      (node (ref "R19") (pin "1") (pinfunction "P$1_1") (pintype "bidirectional"))
      (node (ref "R2") (pin "2") (pinfunction "P$2_2") (pintype "bidirectional"))
      (node (ref "R24") (pin "2") (pinfunction "P$2_2") (pintype "passive"))
      (node (ref "R24") (pin "3") (pinfunction "P$3_3") (pintype "passive"))
      (node (ref "R25") (pin "5") (pinfunction "2_5") (pintype "passive"))
      (node (ref "R25") (pin "8") (pinfunction "2_8") (pintype "passive"))
      (node (ref "R6") (pin "2") (pinfunction "P$2_2") (pintype "bidirectional"))
      (node (ref "R7") (pin "2") (pinfunction "P$2_2") (pintype "bidirectional"))
      (node (ref "U1") (pin "2") (pinfunction "GND_2") (pintype "power_in"))
      (node (ref "U10") (pin "1") (pinfunction "GND_1") (pintype "bidirectional"))
      (node (ref "U11") (pin "3") (pinfunction "GND_3") (pintype "bidirectional"))
      (node (ref "U12") (pin "3") (pinfunction "GND_3") (pintype "passive"))
      (node (ref "U12") (pin "7") (pinfunction "VSS_7") (pintype "passive"))
      (node (ref "U13") (pin "7") (pinfunction "GND_7") (pintype "power_in"))
      (node (ref "U14") (pin "12") (pinfunction "A_12") (pintype "input"))
      (node (ref "U14") (pin "13") (pinfunction "B_13") (pintype "input"))
      (node (ref "U14") (pin "7") (pinfunction "GND_7") (pintype "power_in"))
      (node (ref "U16") (pin "4") (pinfunction "GND_4") (pintype "power_in"))
      (node (ref "U2") (pin "2") (pinfunction "GND_2") (pintype "power_in"))
      (node (ref "U3") (pin "2") (pinfunction "GND_2") (pintype "input"))
      (node (ref "U4") (pin "5") (pinfunction "GND_5") (pintype "bidirectional"))
      (node (ref "U5") (pin "11") (pinfunction "V-_11") (pintype "power_in"))
      (node (ref "U6") (pin "4") (pinfunction "GND_4") (pintype "input"))
      (node (ref "U7") (pin "2") (pinfunction "GND_2") (pintype "power_in"))
      (node (ref "U8") (pin "2") (pinfunction "GND_2") (pintype "power_in"))
      (node (ref "U9") (pin "111") (pinfunction "GND7_111") (pintype "bidirectional"))
      (node (ref "U9") (pin "124") (pinfunction "GND8_124") (pintype "bidirectional"))
      (node (ref "U9") (pin "139") (pinfunction "GND9_139") (pintype "bidirectional"))
      (node (ref "U9") (pin "150") (pinfunction "GND10_150") (pintype "bidirectional"))
      (node (ref "U9") (pin "153") (pinfunction "VREFL_153") (pintype "bidirectional"))
      (node (ref "U9") (pin "156") (pinfunction "AVSS0_156") (pintype "bidirectional"))
      (node (ref "U9") (pin "157") (pinfunction "VREFL0_157") (pintype "bidirectional"))
      (node (ref "U9") (pin "170") (pinfunction "GND11_170") (pintype "bidirectional"))
      (node (ref "U9") (pin "22") (pinfunction "GND1_22") (pintype "bidirectional"))
      (node (ref "U9") (pin "28") (pinfunction "AVSS_USBHS_28") (pintype "bidirectional"))
      (node (ref "U9") (pin "29") (pinfunction "PVSS_USNHS_29") (pintype "bidirectional"))
      (node (ref "U9") (pin "30") (pinfunction "VSS2_USBHS_30") (pintype "bidirectional"))
      (node (ref "U9") (pin "33") (pinfunction "VSS1_USBHS_33") (pintype "bidirectional"))
      (node (ref "U9") (pin "35") (pinfunction "GND2_35") (pintype "bidirectional"))
      (node (ref "U9") (pin "45") (pinfunction "VSS_USB_45") (pintype "bidirectional"))
      (node (ref "U9") (pin "60") (pinfunction "GND3_60") (pintype "bidirectional"))
      (node (ref "U9") (pin "63") (pinfunction "GND4_63") (pintype "bidirectional"))
      (node (ref "U9") (pin "66") (pinfunction "VCC_DCDC_66") (pintype "bidirectional"))
      (node (ref "U9") (pin "83") (pinfunction "GND5_83") (pintype "bidirectional"))
      (node (ref "U9") (pin "98") (pinfunction "GND6_98") (pintype "bidirectional"))
      (node (ref "Y1") (pin "2") (pinfunction "GND_2") (pintype "power_in"))
    )
    (net (code "65") (name "IO_RS485_RXD") (class "Default")
      (node (ref "U4") (pin "1") (pinfunction "R_1") (pintype "bidirectional"))
      (node (ref "U9") (pin "43") (pinfunction "P408/RXD3_A_43") (pintype "bidirectional"))
    )
    (net (code "66") (name "IO_RS485_TE_RE") (class "Default")
      (node (ref "U4") (pin "2") (pinfunction "RE*_2") (pintype "bidirectional"))
      (node (ref "U4") (pin "3") (pinfunction "TE_3") (pintype "bidirectional"))
      (node (ref "U9") (pin "44") (pinfunction "P407_44") (pintype "bidirectional"))
    )
    (net (code "67") (name "IO_RS485_TXD") (class "Default")
      (node (ref "U4") (pin "4") (pinfunction "T_4") (pintype "bidirectional"))
      (node (ref "U9") (pin "42") (pinfunction "P409/TXD3_A_42") (pintype "bidirectional"))
    )
    (net (code "68") (name "LED") (class "Default")
      (node (ref "D7") (pin "C") (pinfunction "1_C") (pintype "passive"))
      (node (ref "U9") (pin "38") (pinfunction "P413_38") (pintype "bidirectional"))
    )
    (net (code "69") (name "Net-(C3-P$1)") (class "Default")
      (node (ref "C2") (pin "+") (pinfunction "+_+") (pintype "passive"))
      (node (ref "C3") (pin "1") (pinfunction "P$1_1") (pintype "bidirectional"))
      (node (ref "D1") (pin "C") (pinfunction "C_C") (pintype "passive"))
      (node (ref "D2") (pin "C") (pinfunction "C_C") (pintype "passive"))
      (node (ref "U3") (pin "1") (pinfunction "IN_1") (pintype "input"))
    )
    (net (code "70") (name "Net-(C28-Pad+)") (class "Default")
      (node (ref "C28") (pin "+") (pinfunction "+_+") (pintype "passive"))
      (node (ref "J3") (pin "1") (pinfunction "1_1") (pintype "passive"))
      (node (ref "PF1") (pin "2") (pinfunction "2_2") (pintype "passive"))
      (node (ref "R18") (pin "1") (pinfunction "1_1") (pintype "passive"))
    )
    (net (code "71") (name "Net-(C45-P$2)") (class "Default")
      (node (ref "C45") (pin "2") (pinfunction "P$2_2") (pintype "bidirectional"))
      (node (ref "D6") (pin "A") (pinfunction "A_A") (pintype "passive"))
      (node (ref "R21") (pin "2") (pinfunction "P$2_2") (pintype "bidirectional"))
      (node (ref "R22") (pin "1") (pinfunction "P$1_1") (pintype "bidirectional"))
      (node (ref "U15") (pin "1") (pinfunction "ADJ_1") (pintype "input"))
    )
    (net (code "72") (name "Net-(D7-2)") (class "Default")
      (node (ref "D7") (pin "A") (pinfunction "2_A") (pintype "passive"))
      (node (ref "R17") (pin "8") (pinfunction "2_8") (pintype "passive"))
    )
    (net (code "73") (name "Net-(EBCLK-TP)") (class "Default")
      (node (ref "EBCLK") (pin "1") (pinfunction "TP_1") (pintype "input"))
      (node (ref "U9") (pin "120") (pinfunction "P602/EBCLK_120") (pintype "bidirectional"))
    )
    (net (code "74") (name "Net-(R1-P$1)") (class "Default")
      (node (ref "R1") (pin "1") (pinfunction "P$1_1") (pintype "bidirectional"))
      (node (ref "R3") (pin "2") (pinfunction "P$2_2") (pintype "bidirectional"))
      (node (ref "U5") (pin "2") (pinfunction "-_2") (pintype "input"))
    )
    (net (code "75") (name "Net-(R2-P$1)") (class "Default")
      (node (ref "R2") (pin "1") (pinfunction "P$1_1") (pintype "bidirectional"))
      (node (ref "R4") (pin "1") (pinfunction "P$1_1") (pintype "bidirectional"))
      (node (ref "U5") (pin "6") (pinfunction "-_6") (pintype "input"))
    )
    (net (code "76") (name "Net-(R5-P$1)") (class "Default")
      (node (ref "J1") (pin "3") (pinfunction "3_3") (pintype "bidirectional"))
      (node (ref "R5") (pin "1") (pinfunction "P$1_1") (pintype "bidirectional"))
      (node (ref "U4") (pin "6") (pinfunction "A_6") (pintype "bidirectional"))
    )
    (net (code "77") (name "Net-(R5-P$2)") (class "Default")
      (node (ref "J1") (pin "4") (pinfunction "4_4") (pintype "bidirectional"))
      (node (ref "R5") (pin "2") (pinfunction "P$2_2") (pintype "bidirectional"))
      (node (ref "U4") (pin "7") (pinfunction "B_7") (pintype "bidirectional"))
    )
    (net (code "78") (name "Net-(R6-P$1)") (class "Default")
      (node (ref "R6") (pin "1") (pinfunction "P$1_1") (pintype "bidirectional"))
      (node (ref "R8") (pin "2") (pinfunction "P$2_2") (pintype "bidirectional"))
      (node (ref "U5") (pin "9") (pinfunction "-_9") (pintype "input"))
    )
    (net (code "79") (name "Net-(R7-P$1)") (class "Default")
      (node (ref "R7") (pin "1") (pinfunction "P$1_1") (pintype "bidirectional"))
      (node (ref "R9") (pin "2") (pinfunction "P$2_2") (pintype "bidirectional"))
      (node (ref "U5") (pin "13") (pinfunction "-_13") (pintype "input"))
    )
    (net (code "80") (name "Net-(R10-P$1)") (class "Default")
      (node (ref "R10") (pin "1") (pinfunction "P$1_1") (pintype "bidirectional"))
      (node (ref "U9") (pin "27") (pinfunction "USBHS_RREF_27") (pintype "bidirectional"))
    )
    (net (code "81") (name "Net-(R12-P$2)") (class "Default")
      (node (ref "R12") (pin "2") (pinfunction "P$2_2") (pintype "bidirectional"))
      (node (ref "U9") (pin "64") (pinfunction "VLO1_64") (pintype "bidirectional"))
      (node (ref "U9") (pin "65") (pinfunction "VLO2_65") (pintype "bidirectional"))
    )
    (net (code "82") (name "Net-(R14-P$2)") (class "Default")
      (node (ref "D3") (pin "2") (pinfunction "2_2") (pintype "passive"))
      (node (ref "J3") (pin "2") (pinfunction "2_2") (pintype "passive"))
      (node (ref "R14") (pin "2") (pinfunction "P$2_2") (pintype "bidirectional"))
      (node (ref "R16") (pin "2") (pinfunction "P$2_2") (pintype "bidirectional"))
    )
    (net (code "83") (name "Net-(R15-P$2)") (class "Default")
      (node (ref "D4") (pin "2") (pinfunction "2_2") (pintype "passive"))
      (node (ref "J3") (pin "3") (pinfunction "3_3") (pintype "passive"))
      (node (ref "R15") (pin "2") (pinfunction "P$2_2") (pintype "bidirectional"))
      (node (ref "R19") (pin "2") (pinfunction "P$2_2") (pintype "bidirectional"))
    )
    (net (code "84") (name "Net-(R17B-2)") (class "Default")
      (node (ref "R17") (pin "7") (pinfunction "2_7") (pintype "passive"))
      (node (ref "U9") (pin "68") (pinfunction "P201/MD_68") (pintype "bidirectional"))
    )
    (net (code "85") (name "Net-(R17C-2)") (class "Default")
      (node (ref "R17") (pin "6") (pinfunction "2_6") (pintype "passive"))
      (node (ref "U9") (pin "69") (pinfunction "P200/NMI_69") (pintype "bidirectional"))
    )
    (net (code "86") (name "Net-(R22-P$2)") (class "Default")
      (node (ref "R22") (pin "2") (pinfunction "P$2_2") (pintype "bidirectional"))
      (node (ref "R23") (pin "2") (pinfunction "P$2_2") (pintype "bidirectional"))
    )
    (net (code "87") (name "Net-(R23-P$1)") (class "Default")
      (node (ref "R23") (pin "1") (pinfunction "P$1_1") (pintype "bidirectional"))
      (node (ref "R24") (pin "1") (pinfunction "P$1_1") (pintype "passive"))
    )
    (net (code "88") (name "Net-(R25B-1)") (class "Default")
      (node (ref "R25") (pin "2") (pinfunction "1_2") (pintype "passive"))
      (node (ref "U9") (pin "169") (pinfunction "P000_169") (pintype "bidirectional"))
    )
    (net (code "89") (name "Net-(R25D-1)") (class "Default")
      (node (ref "R25") (pin "4") (pinfunction "1_4") (pintype "passive"))
      (node (ref "U9") (pin "151") (pinfunction "P015_151") (pintype "bidirectional"))
      (node (ref "U9") (pin "152") (pinfunction "P014_152") (pintype "bidirectional"))
      (node (ref "U9") (pin "159") (pinfunction "P010_159") (pintype "bidirectional"))
      (node (ref "U9") (pin "160") (pinfunction "P009_160") (pintype "bidirectional"))
      (node (ref "U9") (pin "161") (pinfunction "P008_161") (pintype "bidirectional"))
      (node (ref "U9") (pin "162") (pinfunction "P007_162") (pintype "bidirectional"))
      (node (ref "U9") (pin "163") (pinfunction "P006_163") (pintype "bidirectional"))
      (node (ref "U9") (pin "164") (pinfunction "P005_164") (pintype "bidirectional"))
      (node (ref "U9") (pin "165") (pinfunction "P004_165") (pintype "bidirectional"))
      (node (ref "U9") (pin "166") (pinfunction "P003_166") (pintype "bidirectional"))
      (node (ref "U9") (pin "167") (pinfunction "P002_167") (pintype "bidirectional"))
      (node (ref "U9") (pin "168") (pinfunction "P001_168") (pintype "bidirectional"))
    )
    (net (code "90") (name "Net-(TP1-TP)") (class "Default")
      (node (ref "TP1") (pin "1") (pinfunction "TP_1") (pintype "input"))
      (node (ref "U9") (pin "13") (pinfunction "P705_13") (pintype "bidirectional"))
    )
    (net (code "91") (name "Net-(TP2-TP)") (class "Default")
      (node (ref "TP2") (pin "1") (pinfunction "TP_1") (pintype "input"))
      (node (ref "U9") (pin "12") (pinfunction "P704_12") (pintype "bidirectional"))
    )
    (net (code "92") (name "Net-(TP3-TP)") (class "Default")
      (node (ref "TP3") (pin "1") (pinfunction "TP_1") (pintype "input"))
      (node (ref "U9") (pin "11") (pinfunction "P703_11") (pintype "bidirectional"))
    )
    (net (code "93") (name "Net-(TP4-TP)") (class "Default")
      (node (ref "TP4") (pin "1") (pinfunction "TP_1") (pintype "input"))
      (node (ref "U9") (pin "10") (pinfunction "P702_10") (pintype "bidirectional"))
    )
    (net (code "94") (name "Net-(U1-VOUT)") (class "Default")
      (node (ref "U1") (pin "1") (pinfunction "VOUT_1") (pintype "output"))
      (node (ref "U5") (pin "3") (pinfunction "+_3") (pintype "input"))
    )
    (net (code "95") (name "Net-(U2-VOUT)") (class "Default")
      (node (ref "U2") (pin "1") (pinfunction "VOUT_1") (pintype "output"))
      (node (ref "U5") (pin "5") (pinfunction "+_5") (pintype "input"))
    )
    (net (code "96") (name "Net-(U5C-+)") (class "Default")
      (node (ref "U5") (pin "10") (pinfunction "+_10") (pintype "input"))
      (node (ref "U7") (pin "1") (pinfunction "VOUT_1") (pintype "output"))
    )
    (net (code "97") (name "Net-(U5D-+)") (class "Default")
      (node (ref "U5") (pin "12") (pinfunction "+_12") (pintype "input"))
      (node (ref "U8") (pin "1") (pinfunction "VOUT_1") (pintype "output"))
    )
    (net (code "98") (name "Net-(U9-P212{slash}EXTAL)") (class "Default")
      (node (ref "U9") (pin "24") (pinfunction "P212/EXTAL_24") (pintype "bidirectional"))
      (node (ref "Y1") (pin "3") (pinfunction "OUT_3") (pintype "output"))
    )
    (net (code "99") (name "Net-(U9-VCL0)") (class "Default")
      (node (ref "C17") (pin "2") (pinfunction "2_2") (pintype "passive"))
      (node (ref "U9") (pin "19") (pinfunction "VCL0_19") (pintype "bidirectional"))
    )
    (net (code "100") (name "Net-(U9-VCL1)") (class "Default")
      (node (ref "C18") (pin "2") (pinfunction "2_2") (pintype "passive"))
      (node (ref "U9") (pin "62") (pinfunction "VCL1_62") (pintype "bidirectional"))
    )
    (net (code "101") (name "Net-(U9-VCL2)") (class "Default")
      (node (ref "C19") (pin "2") (pinfunction "2_2") (pintype "passive"))
      (node (ref "U9") (pin "148") (pinfunction "VCL2_148") (pintype "bidirectional"))
    )
    (net (code "102") (name "Net-(U9-VCL_F)") (class "Default")
      (node (ref "C21") (pin "2") (pinfunction "2_2") (pintype "passive"))
      (node (ref "U9") (pin "112") (pinfunction "VCL_F_112") (pintype "bidirectional"))
    )
    (net (code "103") (name "Net-(U9-XCIN)") (class "Default")
      (node (ref "R25") (pin "1") (pinfunction "1_1") (pintype "passive"))
      (node (ref "U9") (pin "20") (pinfunction "XCIN_20") (pintype "bidirectional"))
    )
    (net (code "104") (name "Net-(U10-OUT1)") (class "Default")
      (node (ref "C24") (pin "2") (pinfunction "2_2") (pintype "passive"))
      (node (ref "PF1") (pin "1") (pinfunction "1_1") (pintype "passive"))
      (node (ref "U10") (pin "6") (pinfunction "OUT1_6") (pintype "bidirectional"))
      (node (ref "U10") (pin "7") (pinfunction "OUT2_7") (pintype "bidirectional"))
      (node (ref "U10") (pin "8") (pinfunction "OUT3_8") (pintype "bidirectional"))
    )
    (net (code "105") (name "Net-(U13A-Y)") (class "Default")
      (node (ref "U13") (pin "10") (pinfunction "B_10") (pintype "input"))
      (node (ref "U13") (pin "3") (pinfunction "Y_3") (pintype "output"))
    )
    (net (code "106") (name "Net-(U13B-Y)") (class "Default")
      (node (ref "U13") (pin "6") (pinfunction "Y_6") (pintype "output"))
      (node (ref "U13") (pin "9") (pinfunction "A_9") (pintype "input"))
    )
    (net (code "107") (name "Net-(U13C-Y)") (class "Default")
      (node (ref "U13") (pin "12") (pinfunction "A_12") (pintype "input"))
      (node (ref "U13") (pin "8") (pinfunction "Y_8") (pintype "output"))
    )
    (net (code "108") (name "Net-(U13D-B)") (class "Default")
      (node (ref "U13") (pin "13") (pinfunction "B_13") (pintype "input"))
      (node (ref "U14") (pin "8") (pinfunction "Y_8") (pintype "output"))
    )
    (net (code "109") (name "Net-(U14A-Y)") (class "Default")
      (node (ref "U14") (pin "10") (pinfunction "B_10") (pintype "input"))
      (node (ref "U14") (pin "3") (pinfunction "Y_3") (pintype "output"))
    )
    (net (code "110") (name "Net-(U14B-Y)") (class "Default")
      (node (ref "U14") (pin "6") (pinfunction "Y_6") (pintype "output"))
      (node (ref "U14") (pin "9") (pinfunction "A_9") (pintype "input"))
    )
    (net (code "111") (name "OE#") (class "Default")
      (node (ref "J2") (pin "34") (pinfunction "OE#_34") (pintype "input"))
      (node (ref "J6") (pin "2") (pinfunction "2_2") (pintype "passive"))
      (node (ref "U9") (pin "122") (pinfunction "P600/RD_122") (pintype "bidirectional"))
    )
    (net (code "112") (name "QSPI_CS") (class "Default")
      (node (ref "U16") (pin "1") (pinfunction "~{CE}_1") (pintype "input"))
      (node (ref "U9") (pin "141") (pinfunction "P501/QSPI_CS_141") (pintype "bidirectional"))
    )
    (net (code "113") (name "QSPI_D0") (class "Default")
      (node (ref "U16") (pin "5") (pinfunction "SI(IO0)_5") (pintype "bidirectional"))
      (node (ref "U9") (pin "142") (pinfunction "P502/QSPI_IO_0_142") (pintype "bidirectional"))
    )
    (net (code "114") (name "QSPI_D1") (class "Default")
      (node (ref "U16") (pin "2") (pinfunction "SO(IO1)_2") (pintype "bidirectional"))
      (node (ref "U9") (pin "143") (pinfunction "P503/QSPI_IO_1_143") (pintype "bidirectional"))
    )
    (net (code "115") (name "QSPI_D2") (class "Default")
      (node (ref "U16") (pin "3") (pinfunction "~{WP}(IO2)_3") (pintype "bidirectional"))
      (node (ref "U9") (pin "144") (pinfunction "P504/QSPI_IO_2_144") (pintype "bidirectional"))
    )
    (net (code "116") (name "QSPI_D3") (class "Default")
      (node (ref "U16") (pin "7") (pinfunction "~{HOLD}(IO3)_7") (pintype "bidirectional"))
      (node (ref "U9") (pin "145") (pinfunction "P505/QSPI_IO_3_145") (pintype "bidirectional"))
    )
    (net (code "117") (name "QSPI_SCK") (class "Default")
      (node (ref "U16") (pin "6") (pinfunction "SCK_6") (pintype "input"))
      (node (ref "U9") (pin "140") (pinfunction "P500/QSPI_CLK_140") (pintype "bidirectional"))
    )
    (net (code "118") (name "RESET#") (class "Default")
      (node (ref "J4") (pin "15") (pinfunction "15_15") (pintype "passive"))
      (node (ref "R25") (pin "3") (pinfunction "1_3") (pintype "passive"))
      (node (ref "U11") (pin "1") (pinfunction "RESET*_1") (pintype "bidirectional"))
      (node (ref "U9") (pin "67") (pinfunction "~{RESET}_67") (pintype "bidirectional"))
    )
    (net (code "119") (name "RY{slash}BY#") (class "Default")
      (node (ref "J2") (pin "17") (pinfunction "RY/BY#_17") (pintype "output"))
      (node (ref "J6") (pin "5") (pinfunction "5_5") (pintype "passive"))
      (node (ref "U9") (pin "50") (pinfunction "P206/WAIT_50") (pintype "bidirectional"))
    )
    (net (code "120") (name "SCLK") (class "Default")
      (node (ref "U1") (pin "5") (pinfunction "SCLK_5") (pintype "input"))
      (node (ref "U2") (pin "5") (pinfunction "SCLK_5") (pintype "input"))
      (node (ref "U7") (pin "5") (pinfunction "SCLK_5") (pintype "input"))
      (node (ref "U8") (pin "5") (pinfunction "SCLK_5") (pintype "input"))
      (node (ref "U9") (pin "135") (pinfunction "P802_135") (pintype "bidirectional"))
    )
    (net (code "121") (name "SPARE_ANA") (class "Default")
      (node (ref "R9") (pin "1") (pinfunction "P$1_1") (pintype "bidirectional"))
      (node (ref "SPARE_ANA") (pin "1") (pinfunction "TP_1") (pintype "input"))
      (node (ref "U5") (pin "14") (pinfunction "OUT_14") (pintype "output"))
    )
    (net (code "122") (name "SPARE_DAC") (class "Default")
      (node (ref "U8") (pin "4") (pinfunction "DIN_4") (pintype "input"))
      (node (ref "U9") (pin "1") (pinfunction "P400_1") (pintype "bidirectional"))
    )
    (net (code "123") (name "SYNC") (class "Default")
      (node (ref "U1") (pin "6") (pinfunction "SYNC_6") (pintype "input"))
      (node (ref "U2") (pin "6") (pinfunction "SYNC_6") (pintype "input"))
      (node (ref "U7") (pin "6") (pinfunction "SYNC_6") (pintype "input"))
      (node (ref "U8") (pin "6") (pinfunction "SYNC_6") (pintype "input"))
      (node (ref "U9") (pin "136") (pinfunction "P803_136") (pintype "bidirectional"))
    )
    (net (code "124") (name "TCK_SWCLK") (class "Default")
      (node (ref "J4") (pin "9") (pinfunction "9_9") (pintype "passive"))
      (node (ref "R20") (pin "4") (pinfunction "1_4") (pintype "passive"))
      (node (ref "U9") (pin "88") (pinfunction "P300/TCK/SWCLK_88") (pintype "bidirectional"))
    )
    (net (code "125") (name "TDI") (class "Default")
      (node (ref "J4") (pin "5") (pinfunction "5_5") (pintype "passive"))
      (node (ref "R20") (pin "1") (pinfunction "1_1") (pintype "passive"))
      (node (ref "U9") (pin "91") (pinfunction "P110/TDI_91") (pintype "bidirectional"))
    )
    (net (code "126") (name "TDO") (class "Default")
      (node (ref "J4") (pin "13") (pinfunction "13_13") (pintype "passive"))
      (node (ref "R20") (pin "2") (pinfunction "1_2") (pintype "passive"))
      (node (ref "U9") (pin "90") (pinfunction "P109/TDO_90") (pintype "bidirectional"))
    )
    (net (code "127") (name "TMS_SWDIO") (class "Default")
      (node (ref "J4") (pin "7") (pinfunction "7_7") (pintype "passive"))
      (node (ref "R20") (pin "3") (pinfunction "1_3") (pintype "passive"))
      (node (ref "U9") (pin "89") (pinfunction "P108/TMS/SWDIO_89") (pintype "bidirectional"))
    )
    (net (code "128") (name "USB_D_N") (class "Default")
      (node (ref "R14") (pin "1") (pinfunction "P$1_1") (pintype "bidirectional"))
      (node (ref "U9") (pin "31") (pinfunction "USBHS_DM_31") (pintype "bidirectional"))
    )
    (net (code "129") (name "USB_D_P") (class "Default")
      (node (ref "R15") (pin "1") (pinfunction "P$1_1") (pintype "bidirectional"))
      (node (ref "U9") (pin "32") (pinfunction "USBHS_DP_32") (pintype "bidirectional"))
    )
    (net (code "130") (name "USB_OVER_CRNT") (class "Default")
      (node (ref "R11") (pin "2") (pinfunction "P$2_2") (pintype "bidirectional"))
      (node (ref "U10") (pin "5") (pinfunction "OCN_5") (pintype "bidirectional"))
      (node (ref "U9") (pin "15") (pinfunction "P707/USBHS_OVER_CRNT_15") (pintype "bidirectional"))
    )
    (net (code "131") (name "USB_VBUS_EN") (class "Default")
      (node (ref "R13") (pin "2") (pinfunction "P$2_2") (pintype "bidirectional"))
      (node (ref "U10") (pin "4") (pinfunction "EN_4") (pintype "bidirectional"))
      (node (ref "U9") (pin "16") (pinfunction "PB00/USBHS_VBUS_EN_16") (pintype "bidirectional"))
    )
    (net (code "132") (name "VCC") (class "Default")
      (node (ref "C10") (pin "1") (pinfunction "P$1_1") (pintype "bidirectional"))
      (node (ref "C11") (pin "1") (pinfunction "P$1_1") (pintype "bidirectional"))
      (node (ref "C12") (pin "1") (pinfunction "P$1_1") (pintype "bidirectional"))
      (node (ref "C13") (pin "2") (pinfunction "2_2") (pintype "passive"))
      (node (ref "C14") (pin "2") (pinfunction "2_2") (pintype "passive"))
      (node (ref "C15") (pin "1") (pinfunction "P$1_1") (pintype "bidirectional"))
      (node (ref "C23") (pin "2") (pinfunction "2_2") (pintype "passive"))
      (node (ref "C25") (pin "2") (pinfunction "2_2") (pintype "passive"))
      (node (ref "C26") (pin "2") (pinfunction "2_2") (pintype "passive"))
      (node (ref "C27") (pin "2") (pinfunction "2_2") (pintype "passive"))
      (node (ref "C29") (pin "2") (pinfunction "2_2") (pintype "passive"))
      (node (ref "C30") (pin "2") (pinfunction "2_2") (pintype "passive"))
      (node (ref "C31") (pin "2") (pinfunction "2_2") (pintype "passive"))
      (node (ref "C32") (pin "2") (pinfunction "2_2") (pintype "passive"))
      (node (ref "C33") (pin "2") (pinfunction "2_2") (pintype "passive"))
      (node (ref "C34") (pin "2") (pinfunction "2_2") (pintype "passive"))
      (node (ref "C35") (pin "2") (pinfunction "2_2") (pintype "passive"))
      (node (ref "C36") (pin "1") (pinfunction "P$1_1") (pintype "bidirectional"))
      (node (ref "C37") (pin "1") (pinfunction "P$1_1") (pintype "bidirectional"))
      (node (ref "C39") (pin "1") (pinfunction "P$1_1") (pintype "bidirectional"))
      (node (ref "C4") (pin "2") (pinfunction "2_2") (pintype "passive"))
      (node (ref "C40") (pin "1") (pinfunction "P$1_1") (pintype "bidirectional"))
      (node (ref "C5") (pin "2") (pinfunction "2_2") (pintype "passive"))
      (node (ref "C8") (pin "1") (pinfunction "P$1_1") (pintype "bidirectional"))
      (node (ref "C9") (pin "1") (pinfunction "P$1_1") (pintype "bidirectional"))
      (node (ref "J2") (pin "29") (pinfunction "VIO_29") (pintype "power_in"))
      (node (ref "J2") (pin "43") (pinfunction "VCC_43") (pintype "power_in"))
      (node (ref "J4") (pin "1") (pinfunction "1_1") (pintype "passive"))
      (node (ref "J5") (pin "3") (pinfunction "3_3") (pintype "passive"))
      (node (ref "R11") (pin "1") (pinfunction "P$1_1") (pintype "bidirectional"))
      (node (ref "R17") (pin "1") (pinfunction "1_1") (pintype "passive"))
      (node (ref "R17") (pin "2") (pinfunction "1_2") (pintype "passive"))
      (node (ref "R17") (pin "3") (pinfunction "1_3") (pintype "passive"))
      (node (ref "R20") (pin "5") (pinfunction "2_5") (pintype "passive"))
      (node (ref "R20") (pin "6") (pinfunction "2_6") (pintype "passive"))
      (node (ref "R20") (pin "7") (pinfunction "2_7") (pintype "passive"))
      (node (ref "R20") (pin "8") (pinfunction "2_8") (pintype "passive"))
      (node (ref "R25") (pin "6") (pinfunction "2_6") (pintype "passive"))
      (node (ref "R25") (pin "7") (pinfunction "2_7") (pintype "passive"))
      (node (ref "U1") (pin "3") (pinfunction "VA_3") (pintype "power_in"))
      (node (ref "U11") (pin "2") (pinfunction "VCC_2") (pintype "bidirectional"))
      (node (ref "U13") (pin "14") (pinfunction "VCC_14") (pintype "power_in"))
      (node (ref "U14") (pin "14") (pinfunction "VCC_14") (pintype "power_in"))
      (node (ref "U16") (pin "8") (pinfunction "VCC_8") (pintype "power_in"))
      (node (ref "U2") (pin "3") (pinfunction "VA_3") (pintype "power_in"))
      (node (ref "U4") (pin "8") (pinfunction "V_8") (pintype "bidirectional"))
      (node (ref "U6") (pin "3") (pinfunction "OUT_3") (pintype "passive"))
      (node (ref "U7") (pin "3") (pinfunction "VA_3") (pintype "power_in"))
      (node (ref "U8") (pin "3") (pinfunction "VA_3") (pintype "power_in"))
      (node (ref "U9") (pin "110") (pinfunction "VCC5_110") (pintype "bidirectional"))
      (node (ref "U9") (pin "123") (pinfunction "VCC6_123") (pintype "bidirectional"))
      (node (ref "U9") (pin "138") (pinfunction "VCC7_138") (pintype "bidirectional"))
      (node (ref "U9") (pin "149") (pinfunction "VCC8_149") (pintype "bidirectional"))
      (node (ref "U9") (pin "154") (pinfunction "VREFH_154") (pintype "bidirectional"))
      (node (ref "U9") (pin "155") (pinfunction "AVCC0_155") (pintype "bidirectional"))
      (node (ref "U9") (pin "158") (pinfunction "VREFH0_158") (pintype "bidirectional"))
      (node (ref "U9") (pin "171") (pinfunction "VCC9_171") (pintype "bidirectional"))
      (node (ref "U9") (pin "18") (pinfunction "VBATT_18") (pintype "bidirectional"))
      (node (ref "U9") (pin "25") (pinfunction "VCC1_25") (pintype "bidirectional"))
      (node (ref "U9") (pin "26") (pinfunction "AVCC_USBHS_26") (pintype "bidirectional"))
      (node (ref "U9") (pin "34") (pinfunction "VCC_USBHS_34") (pintype "bidirectional"))
      (node (ref "U9") (pin "48") (pinfunction "VCC_USB_48") (pintype "bidirectional"))
      (node (ref "U9") (pin "61") (pinfunction "VCC2_61") (pintype "bidirectional"))
      (node (ref "U9") (pin "84") (pinfunction "VCC3_84") (pintype "bidirectional"))
      (node (ref "U9") (pin "97") (pinfunction "VCC4_97") (pintype "bidirectional"))
      (node (ref "VCC") (pin "1") (pinfunction "TP_1") (pintype "input"))
      (node (ref "Y1") (pin "4") (pinfunction "VDD_4") (pintype "power_in"))
    )
    (net (code "133") (name "VIN") (class "Default")
      (node (ref "C1") (pin "+") (pinfunction "+_+") (pintype "passive"))
      (node (ref "C48") (pin "1") (pinfunction "P$1_1") (pintype "bidirectional"))
      (node (ref "D1") (pin "A") (pinfunction "A_A") (pintype "passive"))
      (node (ref "D5") (pin "C") (pinfunction "C_C") (pintype "passive"))
      (node (ref "J1") (pin "2") (pinfunction "2_2") (pintype "bidirectional"))
      (node (ref "U15") (pin "3") (pinfunction "IN_3") (pintype "input"))
      (node (ref "VIN") (pin "1") (pinfunction "TP_1") (pintype "input"))
    )
    (net (code "134") (name "WE#") (class "Default")
      (node (ref "J2") (pin "13") (pinfunction "WE#_13") (pintype "input"))
      (node (ref "J6") (pin "3") (pinfunction "3_3") (pintype "passive"))
      (node (ref "U9") (pin "121") (pinfunction "P601/WR/WR0_121") (pintype "bidirectional"))
    )
    (net (code "135") (name "WP_ACC_ANA") (class "Default")
      (node (ref "J2") (pin "16") (pinfunction "WP#_16") (pintype "input"))
      (node (ref "J6") (pin "4") (pinfunction "4_4") (pintype "passive"))
      (node (ref "R4") (pin "2") (pinfunction "P$2_2") (pintype "bidirectional"))
      (node (ref "U5") (pin "7") (pinfunction "OUT_7") (pintype "output"))
    )
    (net (code "136") (name "WP_ACC_DAC") (class "Default")
      (node (ref "U2") (pin "4") (pinfunction "DIN_4") (pintype "input"))
      (node (ref "U9") (pin "175") (pinfunction "P512/TXD4_B/SDA4_B_175") (pintype "bidirectional"))
    )
    (net (code "137") (name "unconnected-(J4-Pad2)") (class "Default")
      (node (ref "J4") (pin "2") (pinfunction "2_2") (pintype "passive"))
    )
    (net (code "138") (name "unconnected-(J4-Pad3)") (class "Default")
      (node (ref "J4") (pin "3") (pinfunction "3_3") (pintype "passive"))
    )
    (net (code "139") (name "unconnected-(J4-Pad11)") (class "Default")
      (node (ref "J4") (pin "11") (pinfunction "11_11") (pintype "passive"))
    )
    (net (code "140") (name "unconnected-(J4-Pad17)") (class "Default")
      (node (ref "J4") (pin "17") (pinfunction "17_17") (pintype "passive"))
    )
    (net (code "141") (name "unconnected-(J4-Pad19)") (class "Default")
      (node (ref "J4") (pin "19") (pinfunction "19_19") (pintype "passive"))
    )
    (net (code "142") (name "unconnected-(J6-Pad6)") (class "Default")
      (node (ref "J6") (pin "6") (pinfunction "6_6") (pintype "passive"))
    )
    (net (code "143") (name "unconnected-(J6-Pad7)") (class "Default")
      (node (ref "J6") (pin "7") (pinfunction "7_7") (pintype "passive"))
    )
    (net (code "144") (name "unconnected-(J6-Pad8)") (class "Default")
      (node (ref "J6") (pin "8") (pinfunction "8_8") (pintype "passive"))
    )
    (net (code "145") (name "unconnected-(U9-P202-Pad54)") (class "Default")
      (node (ref "U9") (pin "54") (pinfunction "P202_54") (pintype "bidirectional"))
    )
    (net (code "146") (name "unconnected-(U9-P213{slash}XTAL{slash}TXD-Pad23)") (class "Default")
      (node (ref "U9") (pin "23") (pinfunction "P213/XTAL/TXD_23") (pintype "bidirectional"))
    )
    (net (code "147") (name "unconnected-(U9-P401-Pad2)") (class "Default")
      (node (ref "U9") (pin "2") (pinfunction "P401_2") (pintype "bidirectional"))
    )
    (net (code "148") (name "unconnected-(U9-P402-Pad3)") (class "Default")
      (node (ref "U9") (pin "3") (pinfunction "P402_3") (pintype "bidirectional"))
    )
    (net (code "149") (name "unconnected-(U9-P403-Pad4)") (class "Default")
      (node (ref "U9") (pin "4") (pinfunction "P403_4") (pintype "bidirectional"))
    )
    (net (code "150") (name "unconnected-(U9-P404-Pad5)") (class "Default")
      (node (ref "U9") (pin "5") (pinfunction "P404_5") (pintype "bidirectional"))
    )
    (net (code "151") (name "unconnected-(U9-P405-Pad6)") (class "Default")
      (node (ref "U9") (pin "6") (pinfunction "P405_6") (pintype "bidirectional"))
    )
    (net (code "152") (name "unconnected-(U9-P406-Pad7)") (class "Default")
      (node (ref "U9") (pin "7") (pinfunction "P406_7") (pintype "bidirectional"))
    )
    (net (code "153") (name "unconnected-(U9-P412-Pad39)") (class "Default")
      (node (ref "U9") (pin "39") (pinfunction "P412_39") (pintype "bidirectional"))
    )
    (net (code "154") (name "unconnected-(U9-P414-Pad37)") (class "Default")
      (node (ref "U9") (pin "37") (pinfunction "P414_37") (pintype "bidirectional"))
    )
    (net (code "155") (name "unconnected-(U9-P415-Pad36)") (class "Default")
      (node (ref "U9") (pin "36") (pinfunction "P415_36") (pintype "bidirectional"))
    )
    (net (code "156") (name "unconnected-(U9-P506-Pad146)") (class "Default")
      (node (ref "U9") (pin "146") (pinfunction "P506_146") (pintype "bidirectional"))
    )
    (net (code "157") (name "unconnected-(U9-P507-Pad147)") (class "Default")
      (node (ref "U9") (pin "147") (pinfunction "P507_147") (pintype "bidirectional"))
    )
    (net (code "158") (name "unconnected-(U9-P608{slash}A00{slash}BC0-Pad99)") (class "Default")
      (node (ref "U9") (pin "99") (pinfunction "P608/A00/BC0_99") (pintype "bidirectional"))
    )
    (net (code "159") (name "unconnected-(U9-P700-Pad8)") (class "Default")
      (node (ref "U9") (pin "8") (pinfunction "P700_8") (pintype "bidirectional"))
    )
    (net (code "160") (name "unconnected-(U9-P701-Pad9)") (class "Default")
      (node (ref "U9") (pin "9") (pinfunction "P701_9") (pintype "bidirectional"))
    )
    (net (code "161") (name "unconnected-(U9-P706{slash}IRQ_7-Pad14)") (class "Default")
      (node (ref "U9") (pin "14") (pinfunction "P706/IRQ_7_14") (pintype "bidirectional"))
    )
    (net (code "162") (name "unconnected-(U9-P805-Pad173)") (class "Default")
      (node (ref "U9") (pin "173") (pinfunction "P805_173") (pintype "bidirectional"))
    )
    (net (code "163") (name "unconnected-(U9-P806-Pad172)") (class "Default")
      (node (ref "U9") (pin "172") (pinfunction "P806_172") (pintype "bidirectional"))
    )
    (net (code "164") (name "unconnected-(U9-P901-Pad59)") (class "Default")
      (node (ref "U9") (pin "59") (pinfunction "P901_59") (pintype "bidirectional"))
    )
    (net (code "165") (name "unconnected-(U9-PA00-Pad114)") (class "Default")
      (node (ref "U9") (pin "114") (pinfunction "PA00_114") (pintype "bidirectional"))
    )
    (net (code "166") (name "unconnected-(U9-PA01-Pad113)") (class "Default")
      (node (ref "U9") (pin "113") (pinfunction "PA01_113") (pintype "bidirectional"))
    )
    (net (code "167") (name "unconnected-(U9-PA08-Pad107)") (class "Default")
      (node (ref "U9") (pin "107") (pinfunction "PA08_107") (pintype "bidirectional"))
    )
    (net (code "168") (name "unconnected-(U9-PA09-Pad108)") (class "Default")
      (node (ref "U9") (pin "108") (pinfunction "PA09_108") (pintype "bidirectional"))
    )
    (net (code "169") (name "unconnected-(U9-PA10-Pad109)") (class "Default")
      (node (ref "U9") (pin "109") (pinfunction "PA10_109") (pintype "bidirectional"))
    )
    (net (code "170") (name "unconnected-(U9-PB01{slash}USBHS_VBUS-Pad17)") (class "Default")
      (node (ref "U9") (pin "17") (pinfunction "PB01/USBHS_VBUS_17") (pintype "bidirectional"))
    )
    (net (code "171") (name "unconnected-(U9-USB_DM-Pad46)") (class "Default")
      (node (ref "U9") (pin "46") (pinfunction "USB_DM_46") (pintype "bidirectional"))
    )
    (net (code "172") (name "unconnected-(U9-USB_DP-Pad47)") (class "Default")
      (node (ref "U9") (pin "47") (pinfunction "USB_DP_47") (pintype "bidirectional"))
    )
    (net (code "173") (name "unconnected-(U9-XCOUT-Pad21)") (class "Default")
      (node (ref "U9") (pin "21") (pinfunction "XCOUT_21") (pintype "bidirectional"))
    )
    (net (code "174") (name "unconnected-(U12-NC-Pad5)") (class "Default")
      (node (ref "U12") (pin "5") (pinfunction "NC_5") (pintype "no_connect"))
    )
    (net (code "175") (name "unconnected-(U14D-Y-Pad11)") (class "Default")
      (node (ref "U14") (pin "11") (pinfunction "Y_11") (pintype "output"))
    )
    (net (code "176") (name "unconnected-(Y1-CTL-Pad1)") (class "Default")
      (node (ref "Y1") (pin "1") (pinfunction "CTL_1") (pintype "passive"))
    )
  )
)
